# untitled.net
KiCad netlist of a schematic drawn in EAGLE
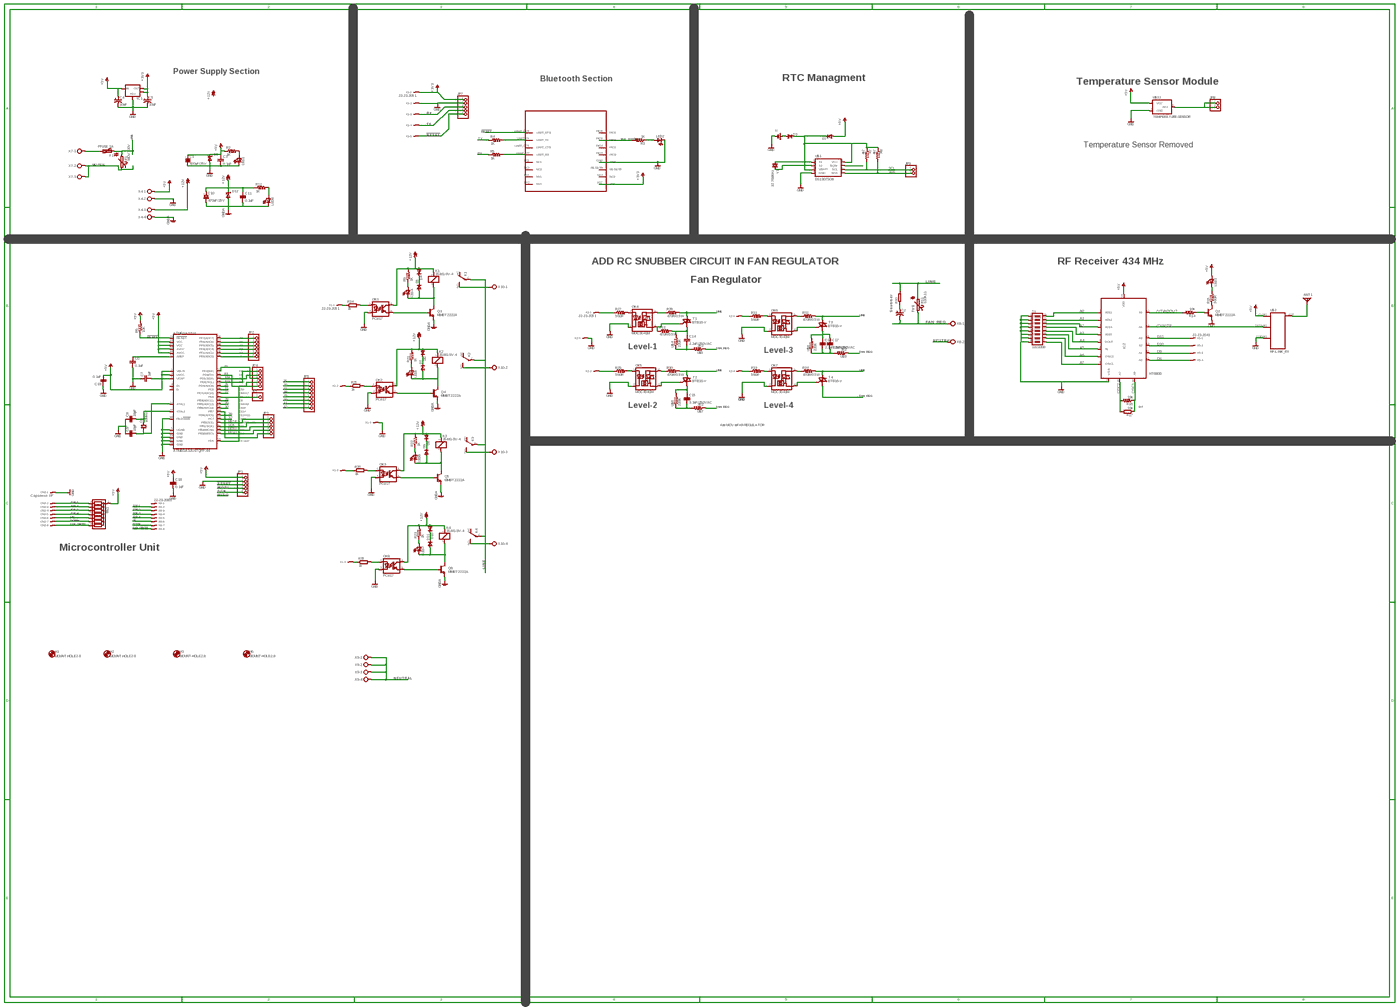
[diagram p0: schematic, sheet 1, overview]
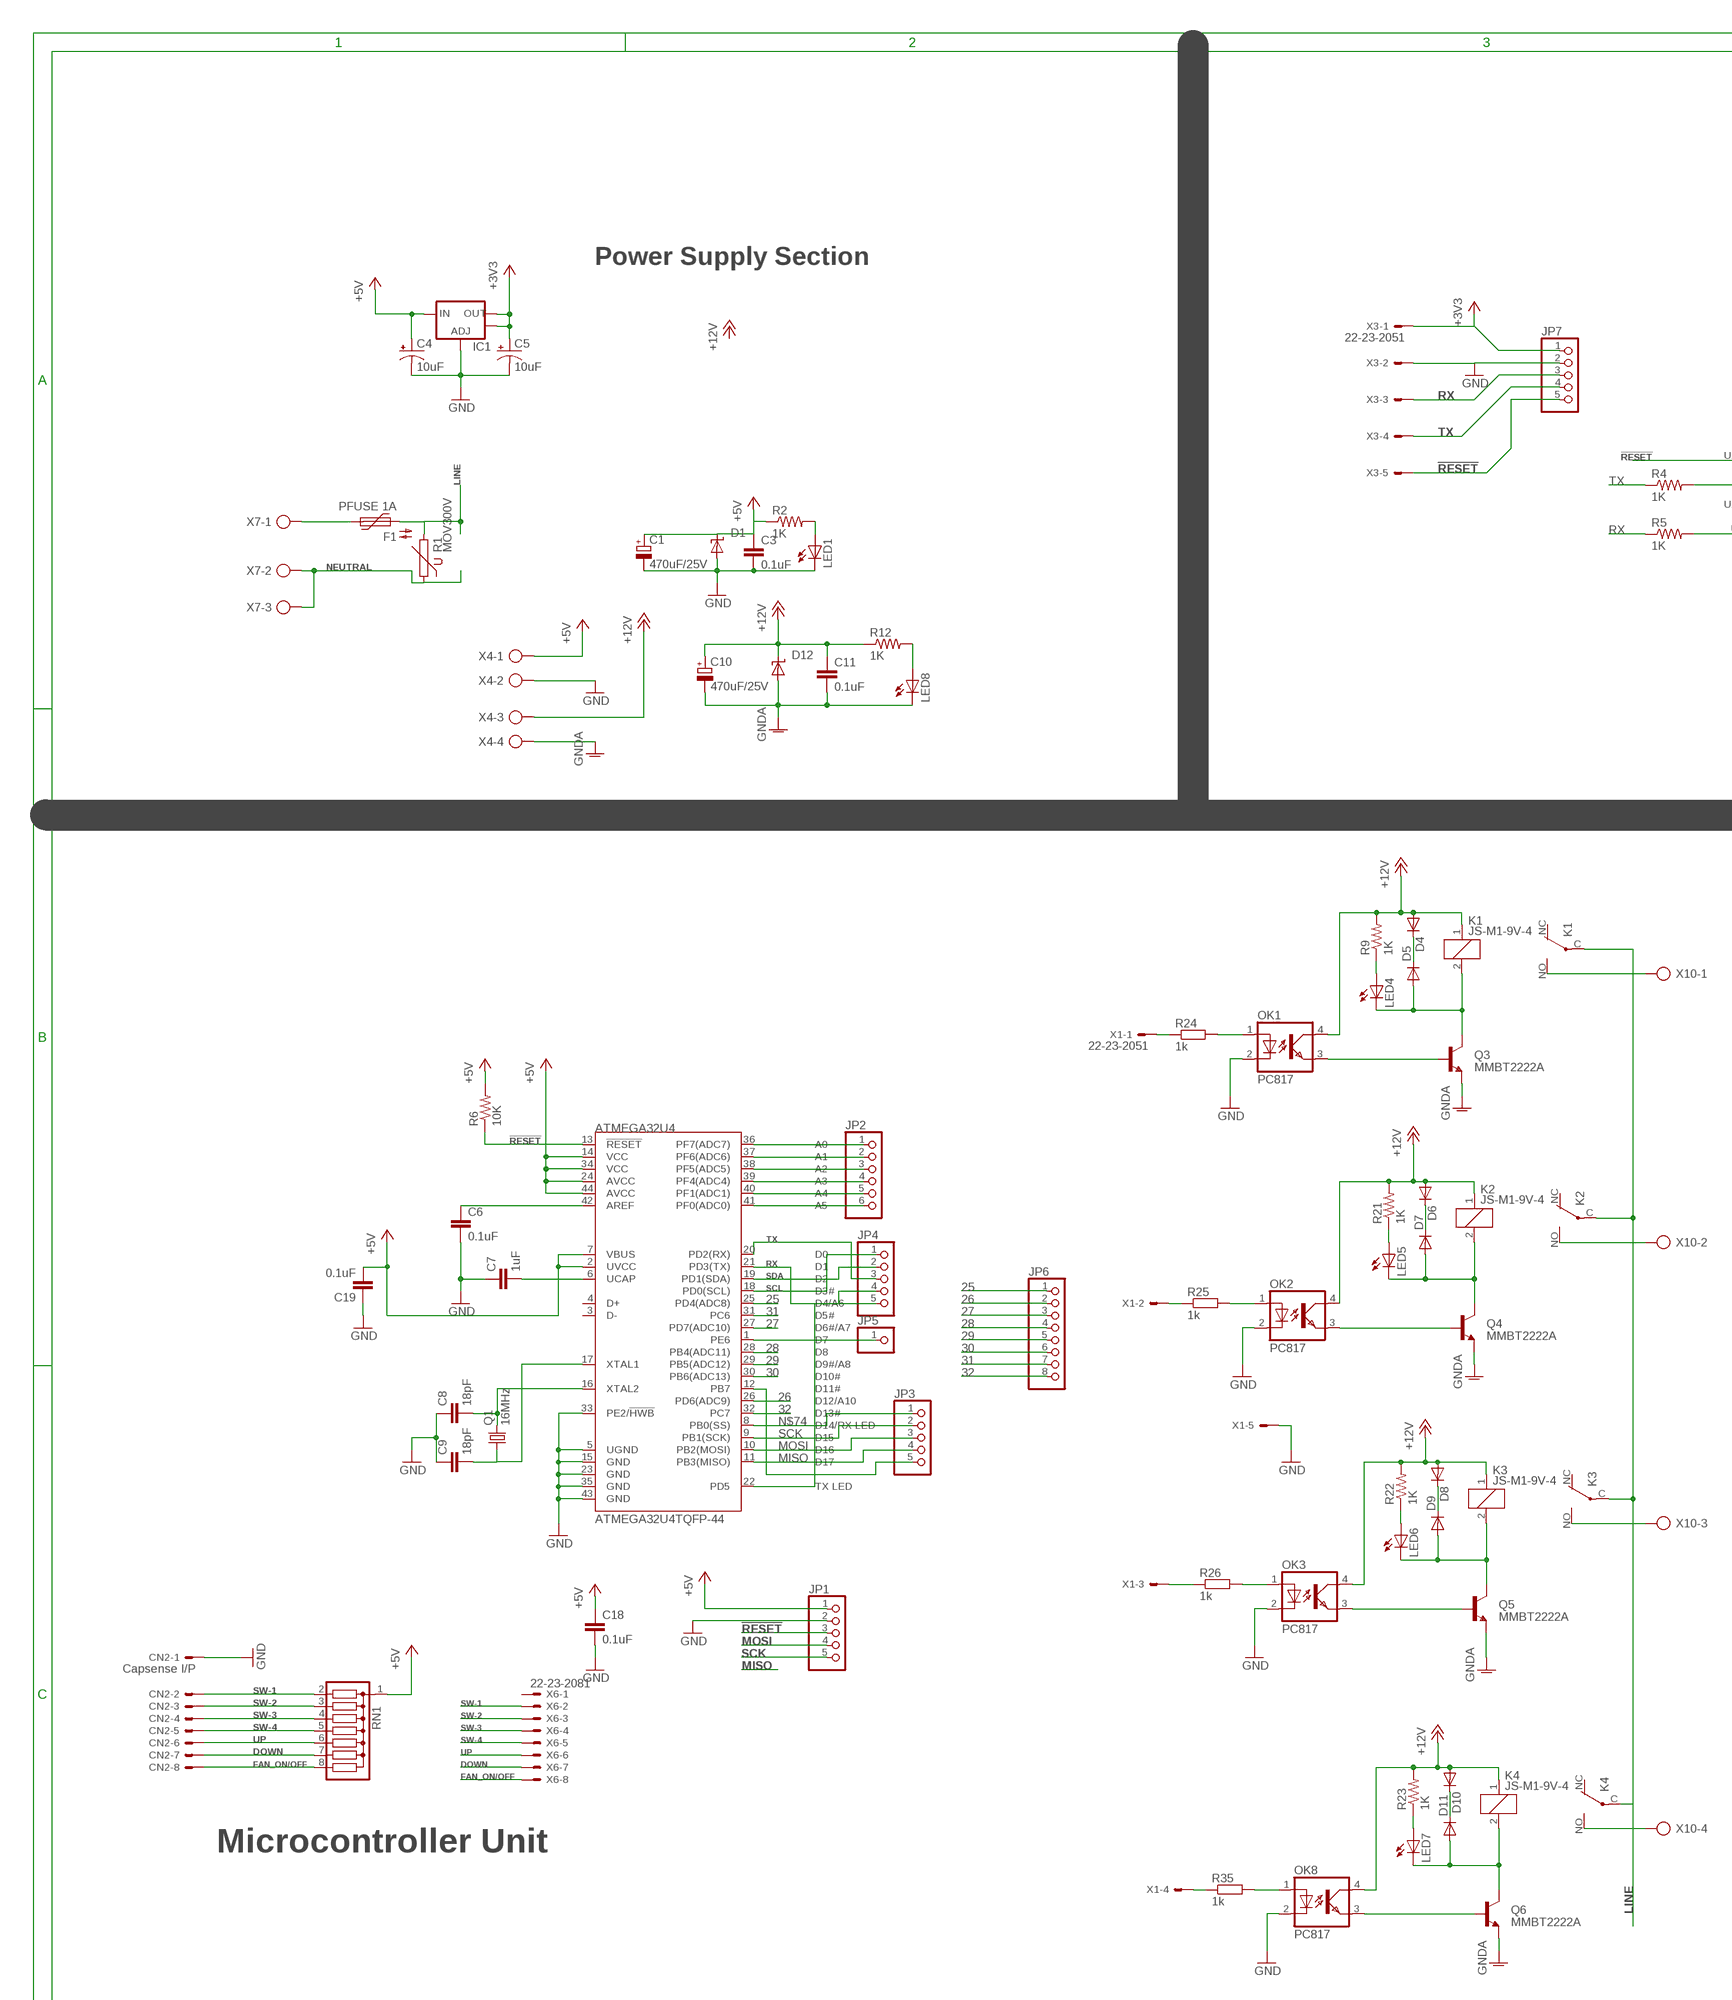
[diagram p1: schematic, sheet 1, part 1 of 6]
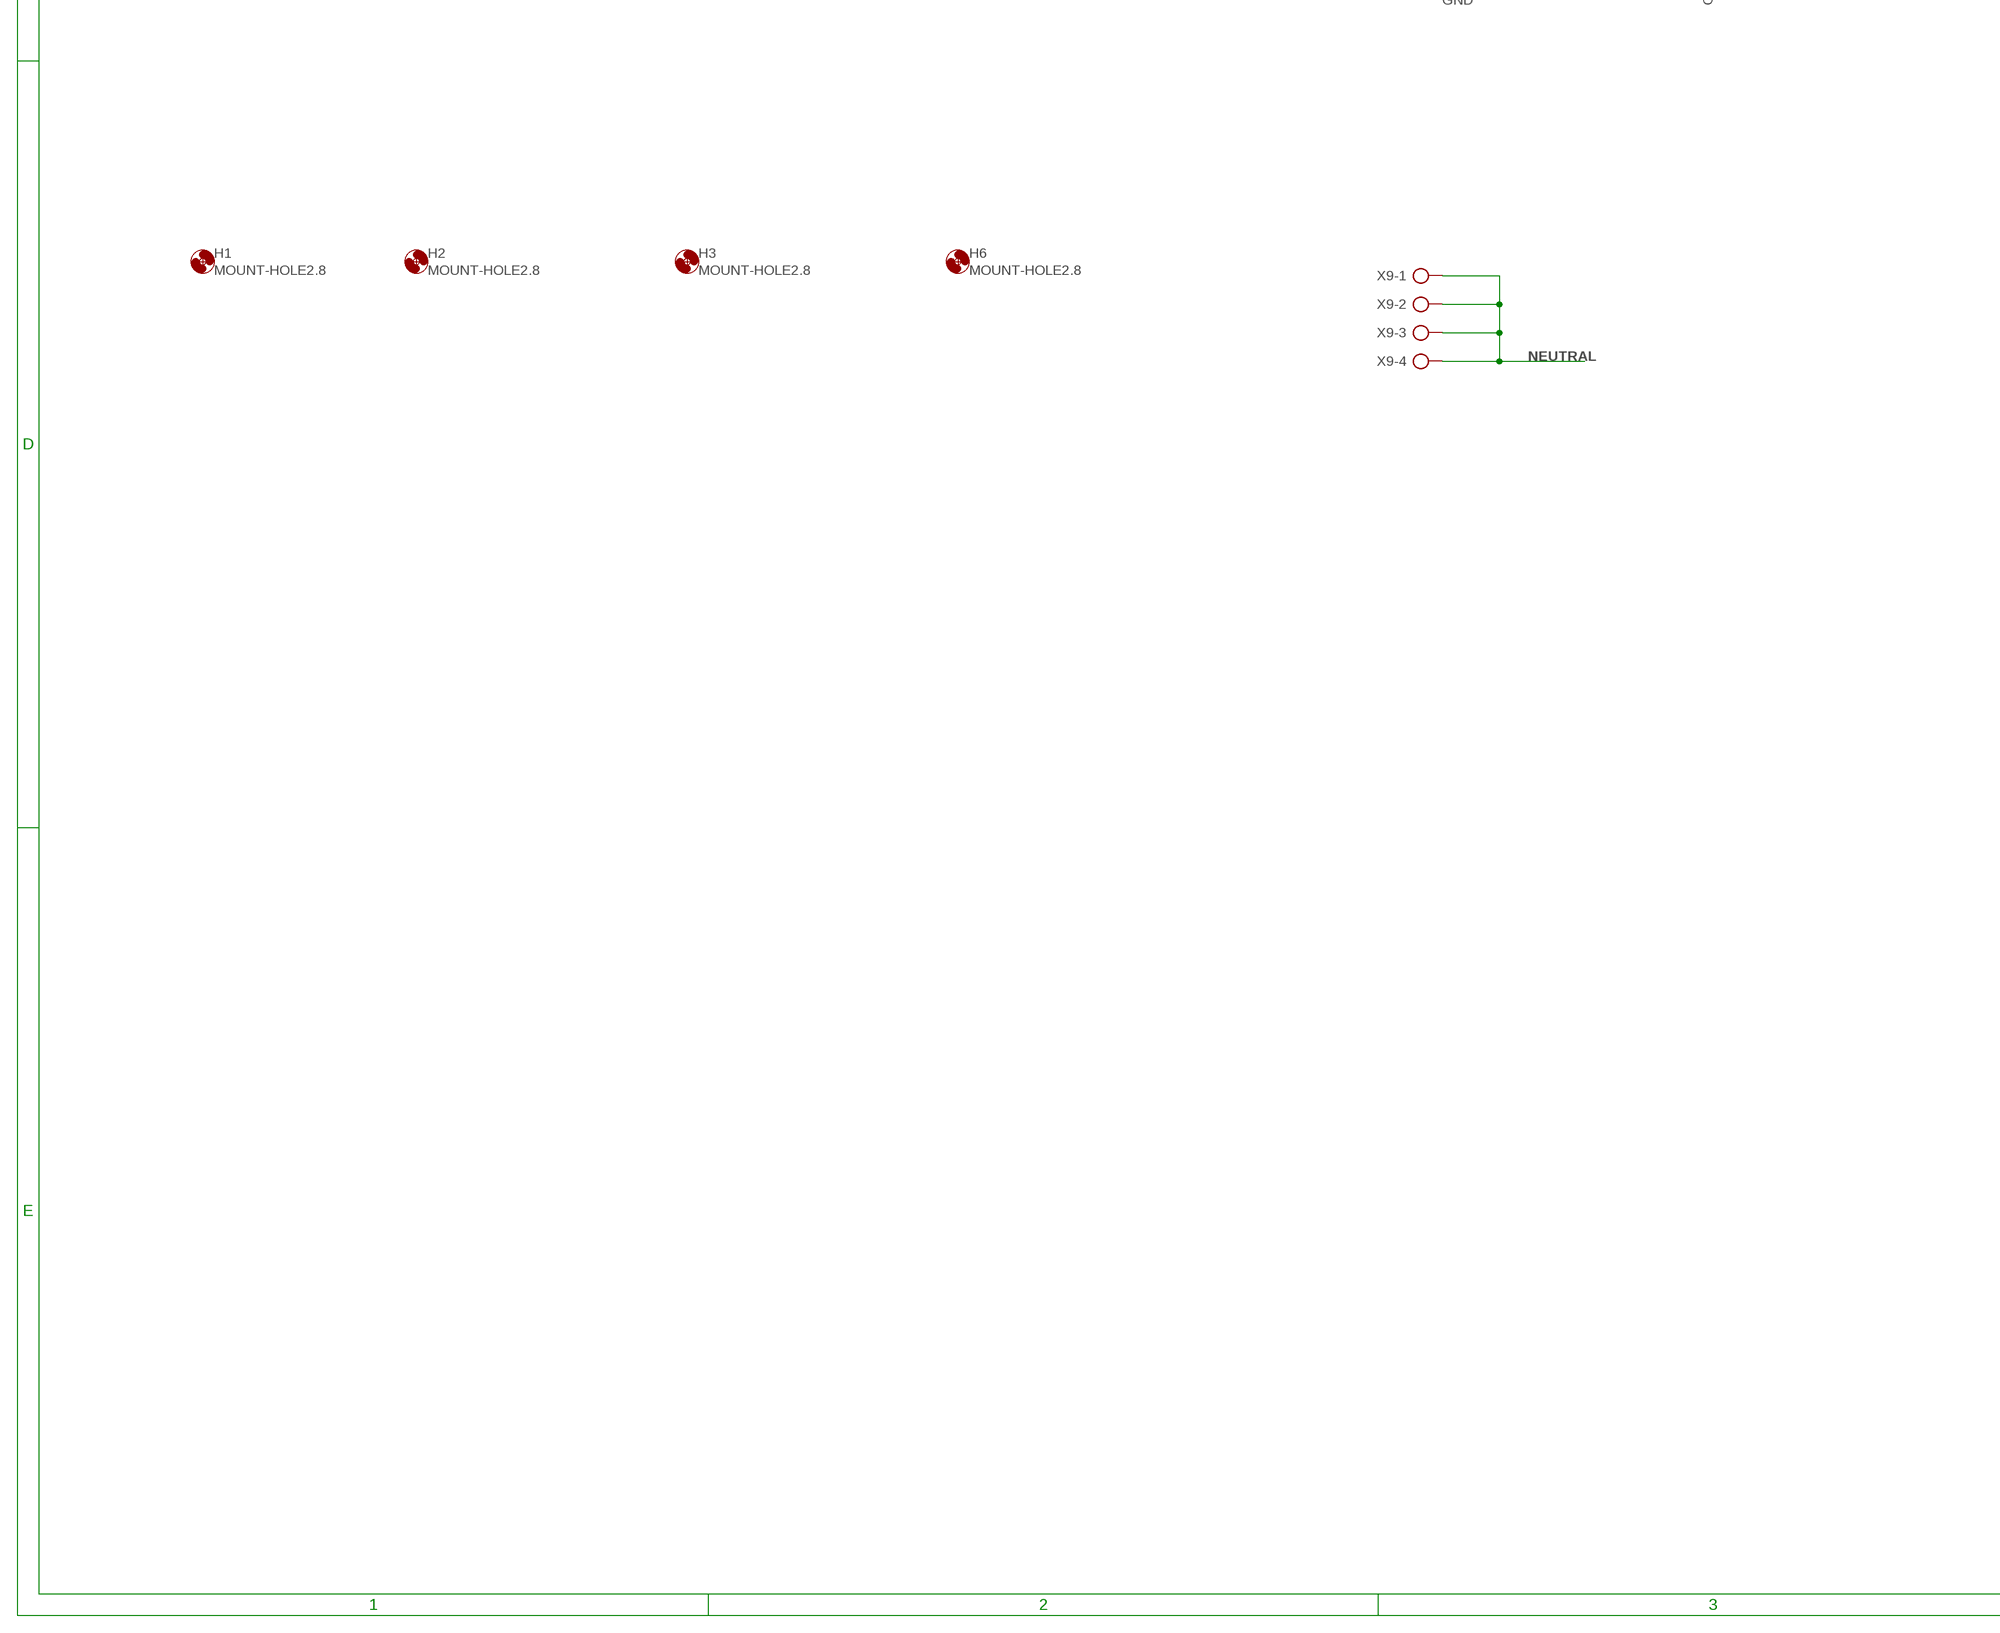
[diagram p2: schematic, sheet 1, part 2 of 6]
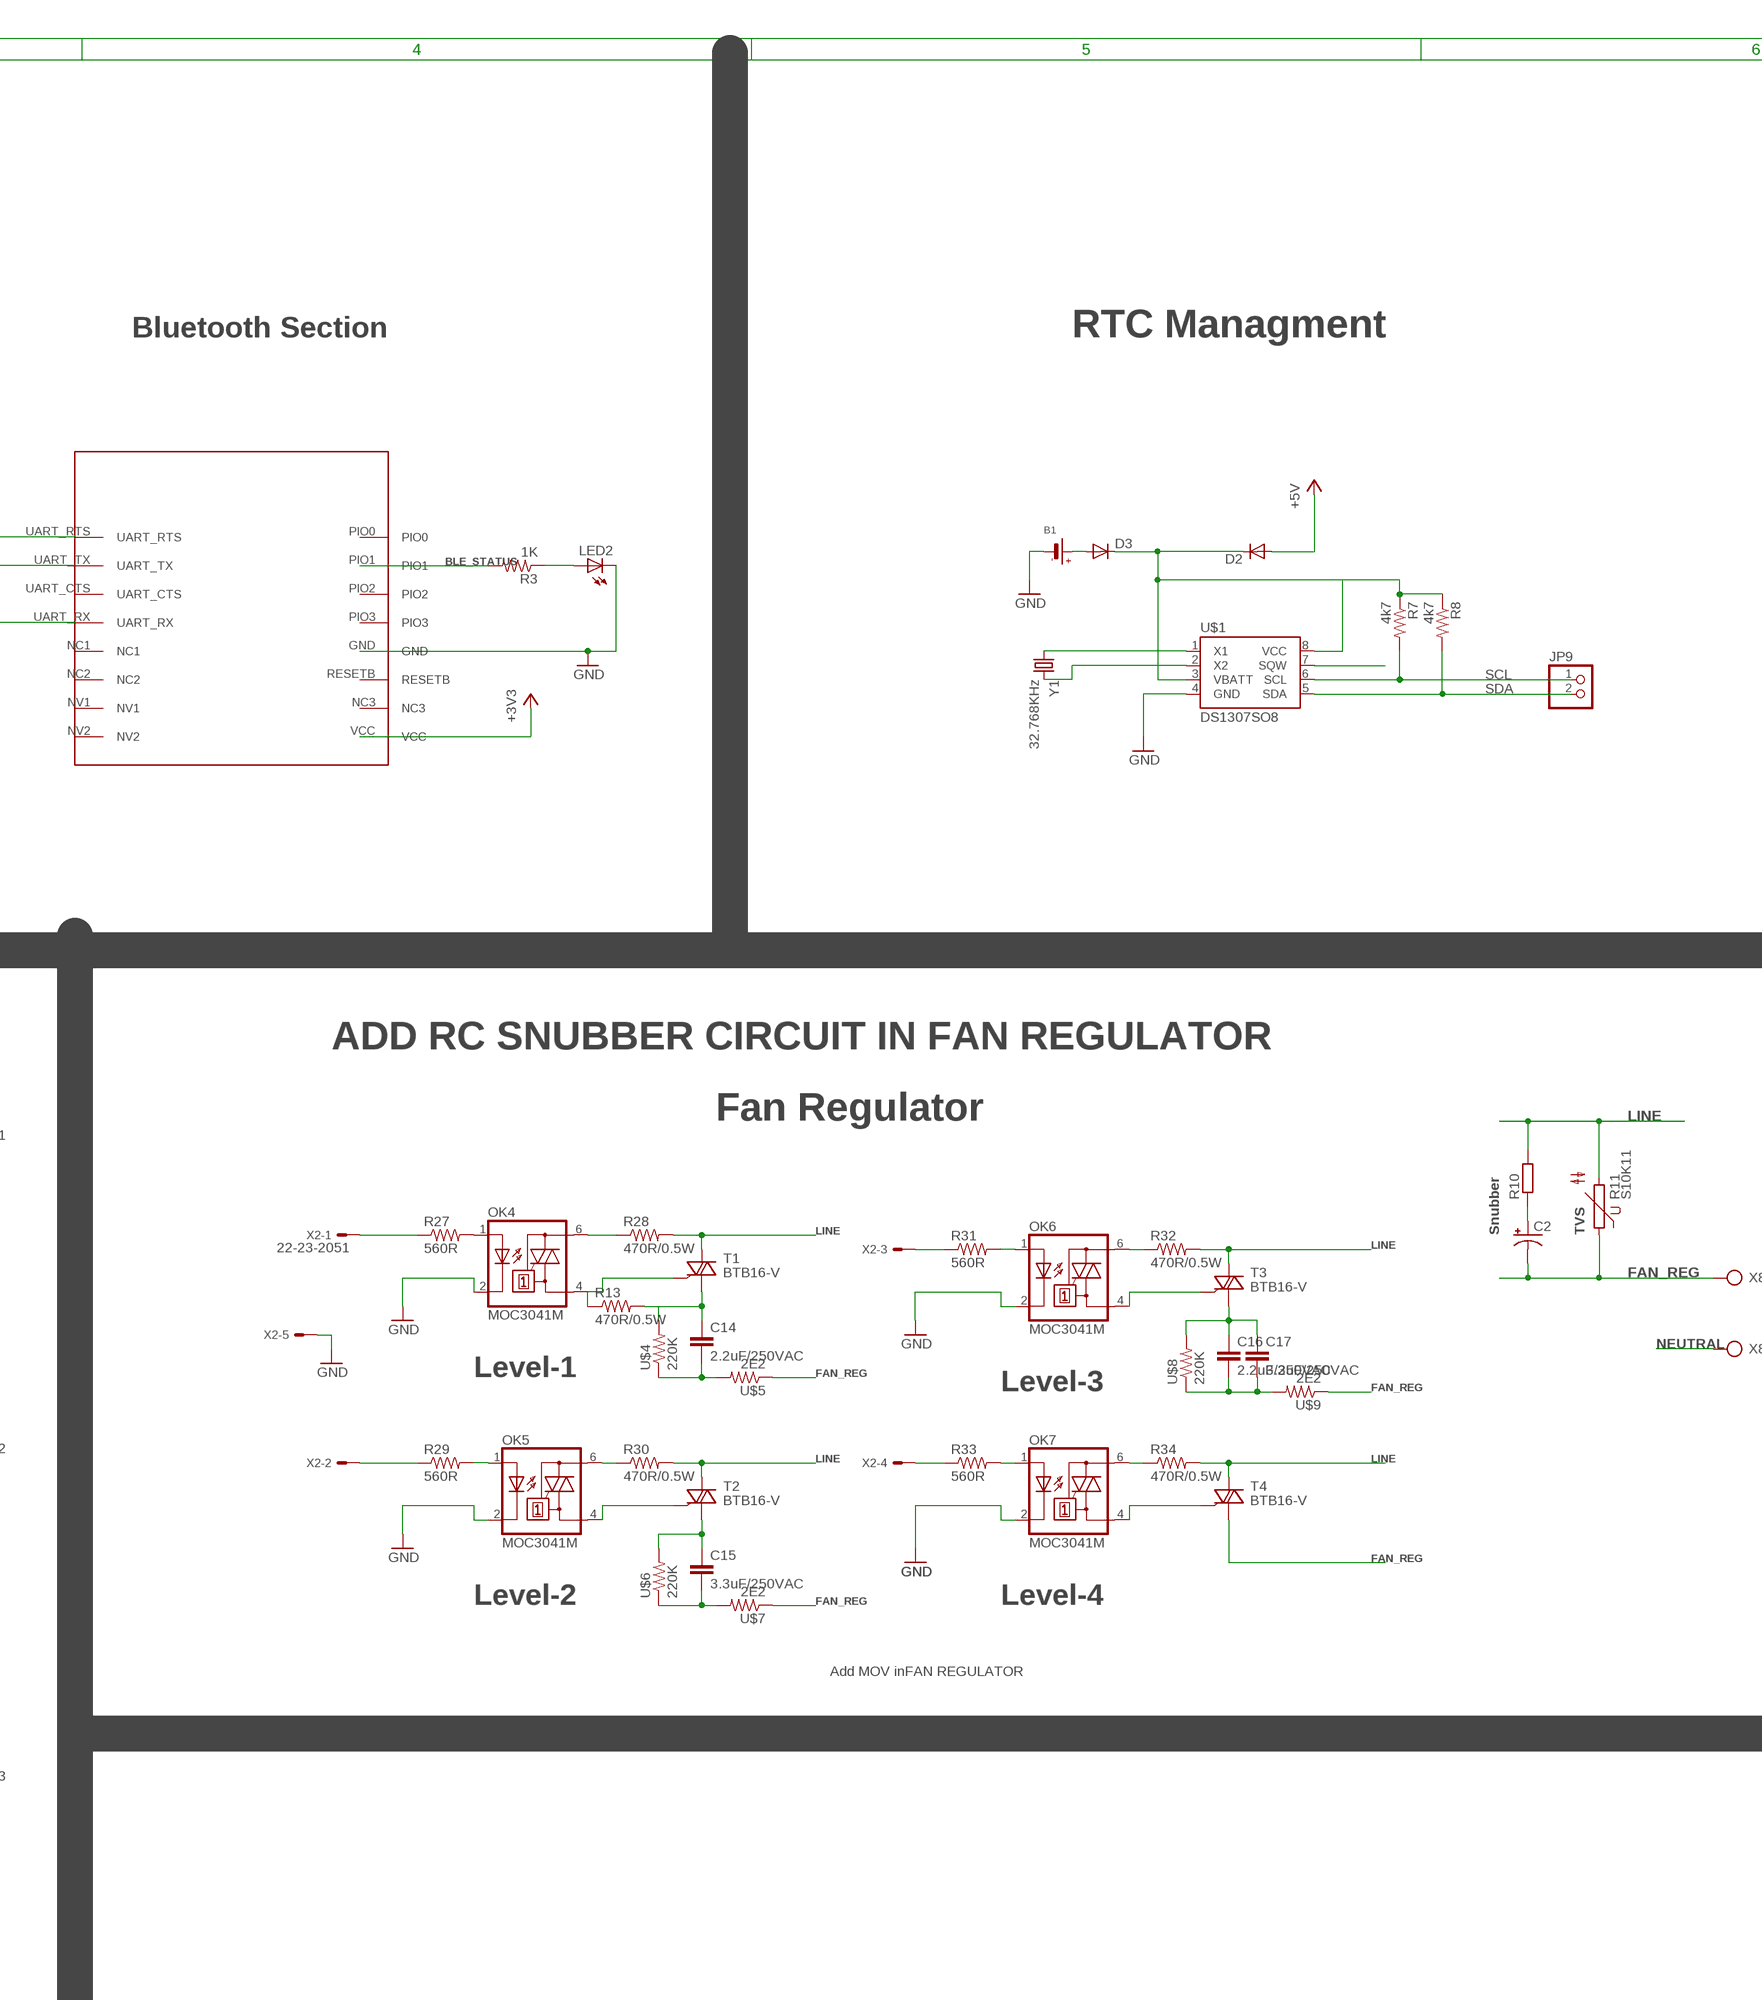
[diagram p3: schematic, sheet 1, part 3 of 6]
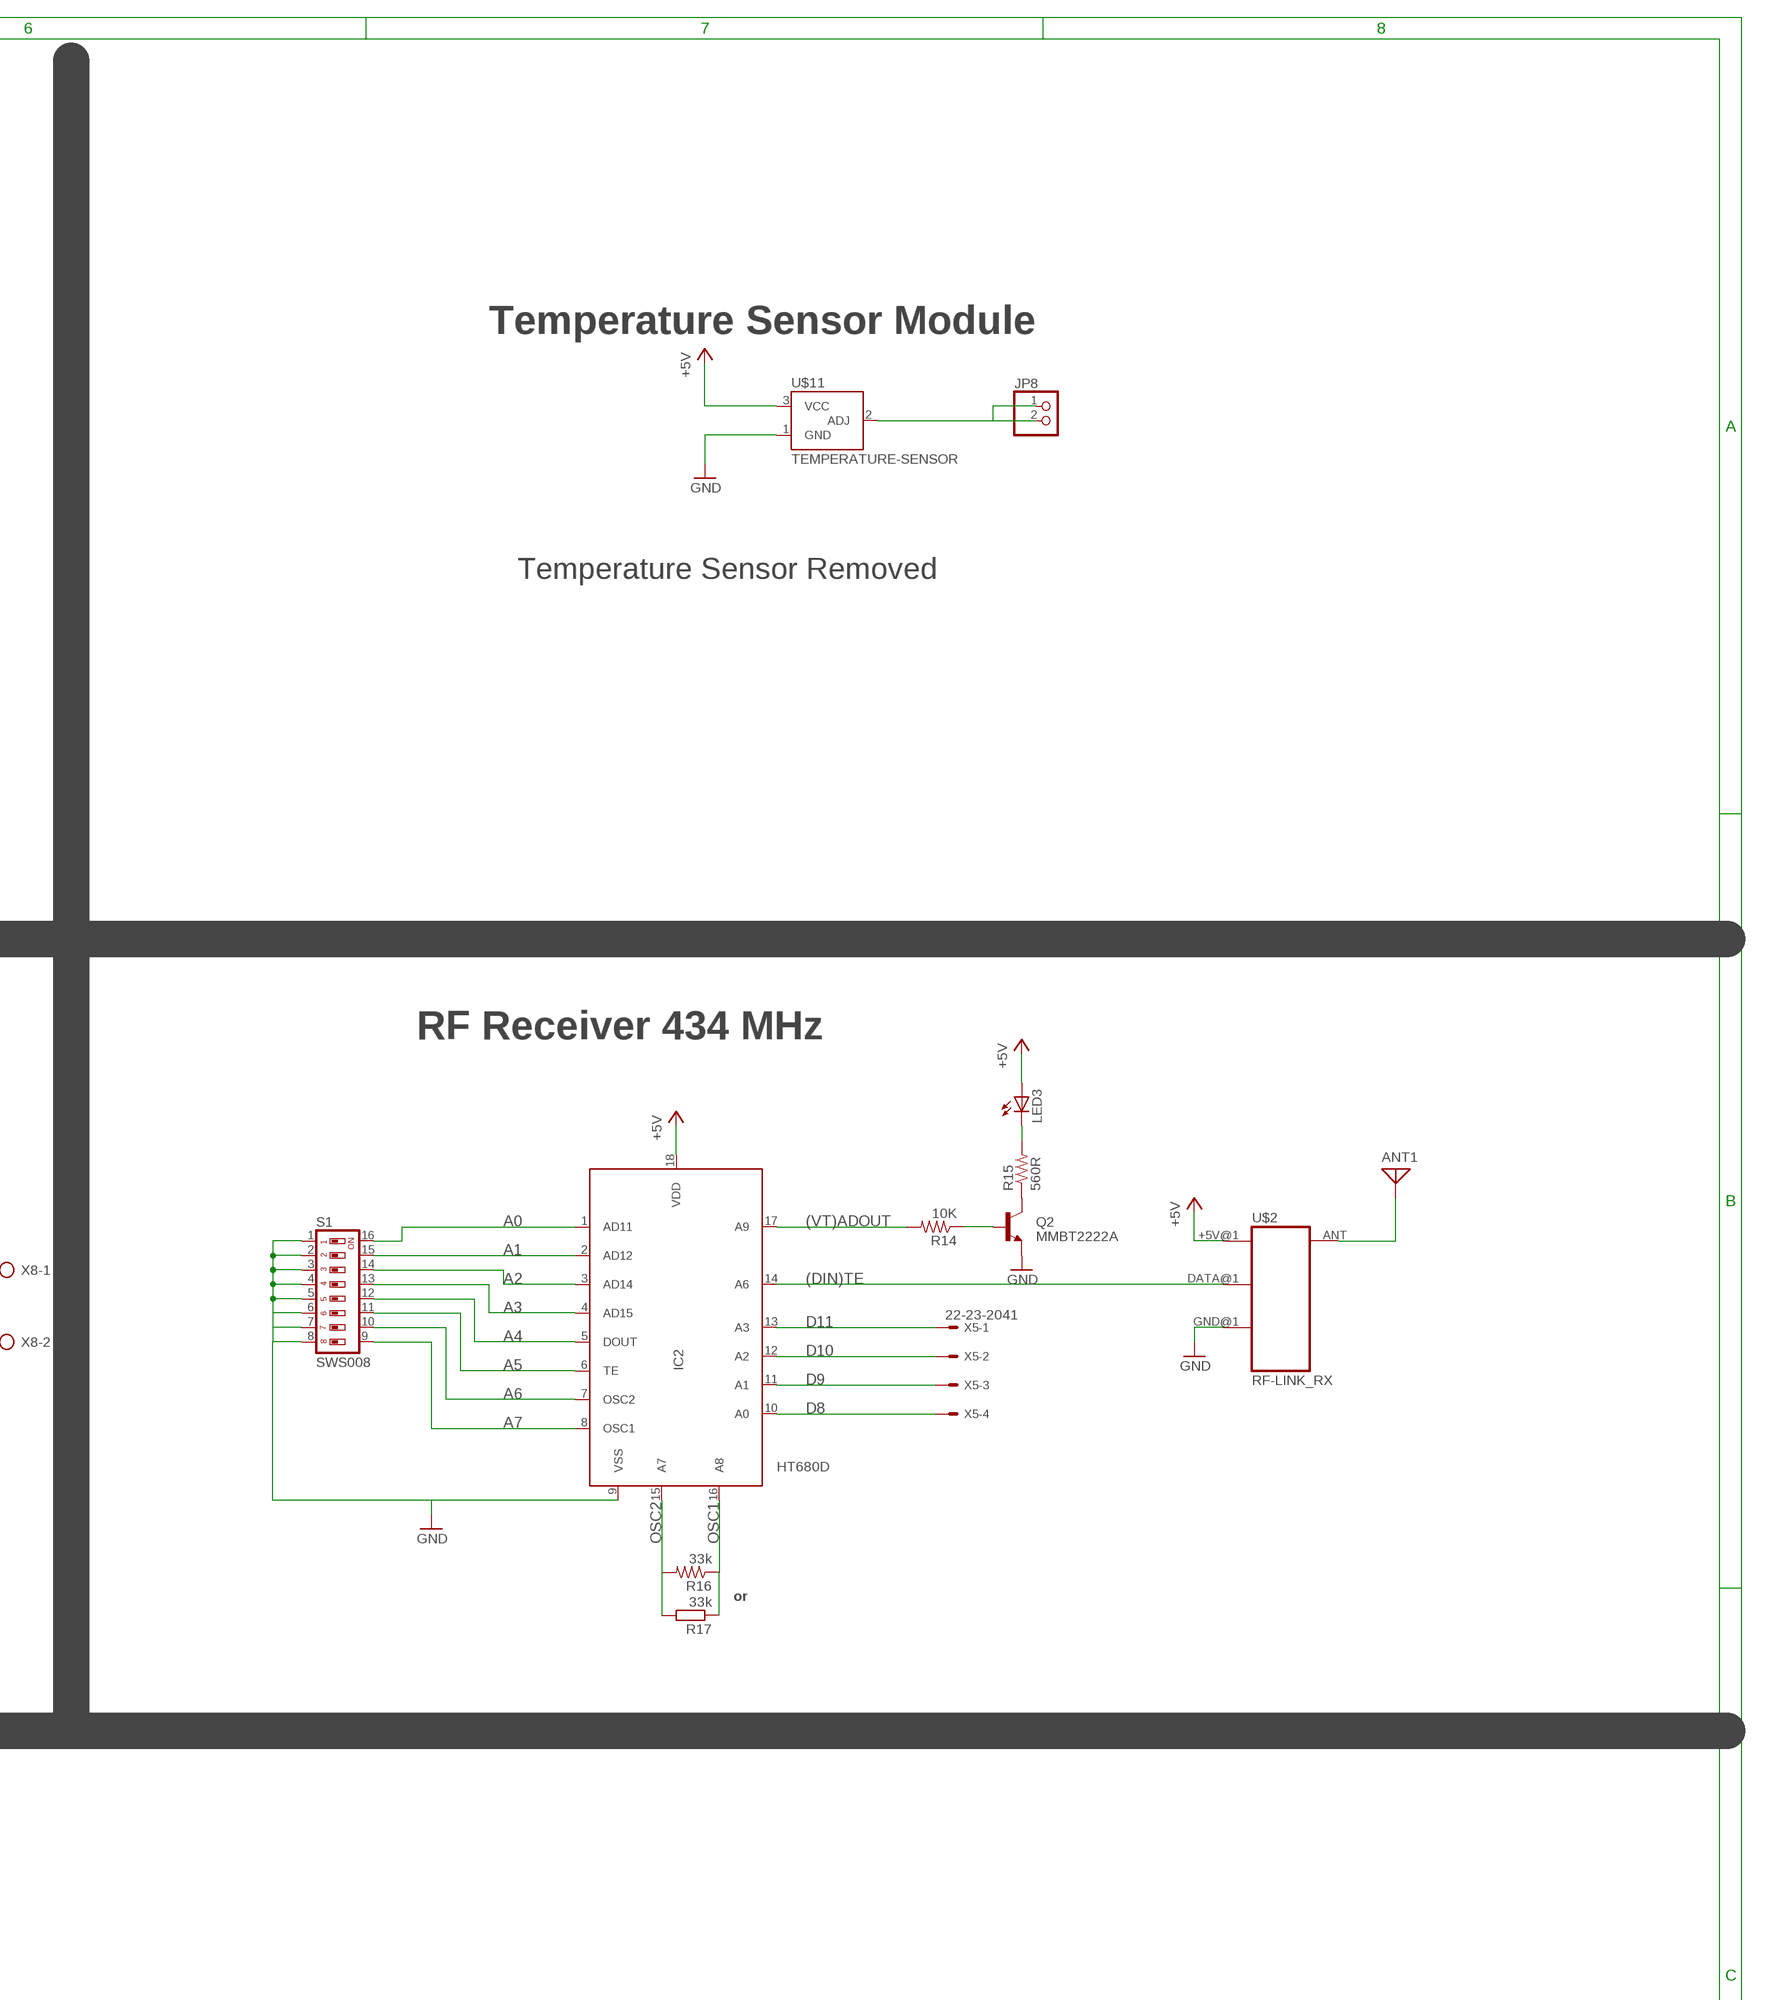
[diagram p4: schematic, sheet 1, part 4 of 6]
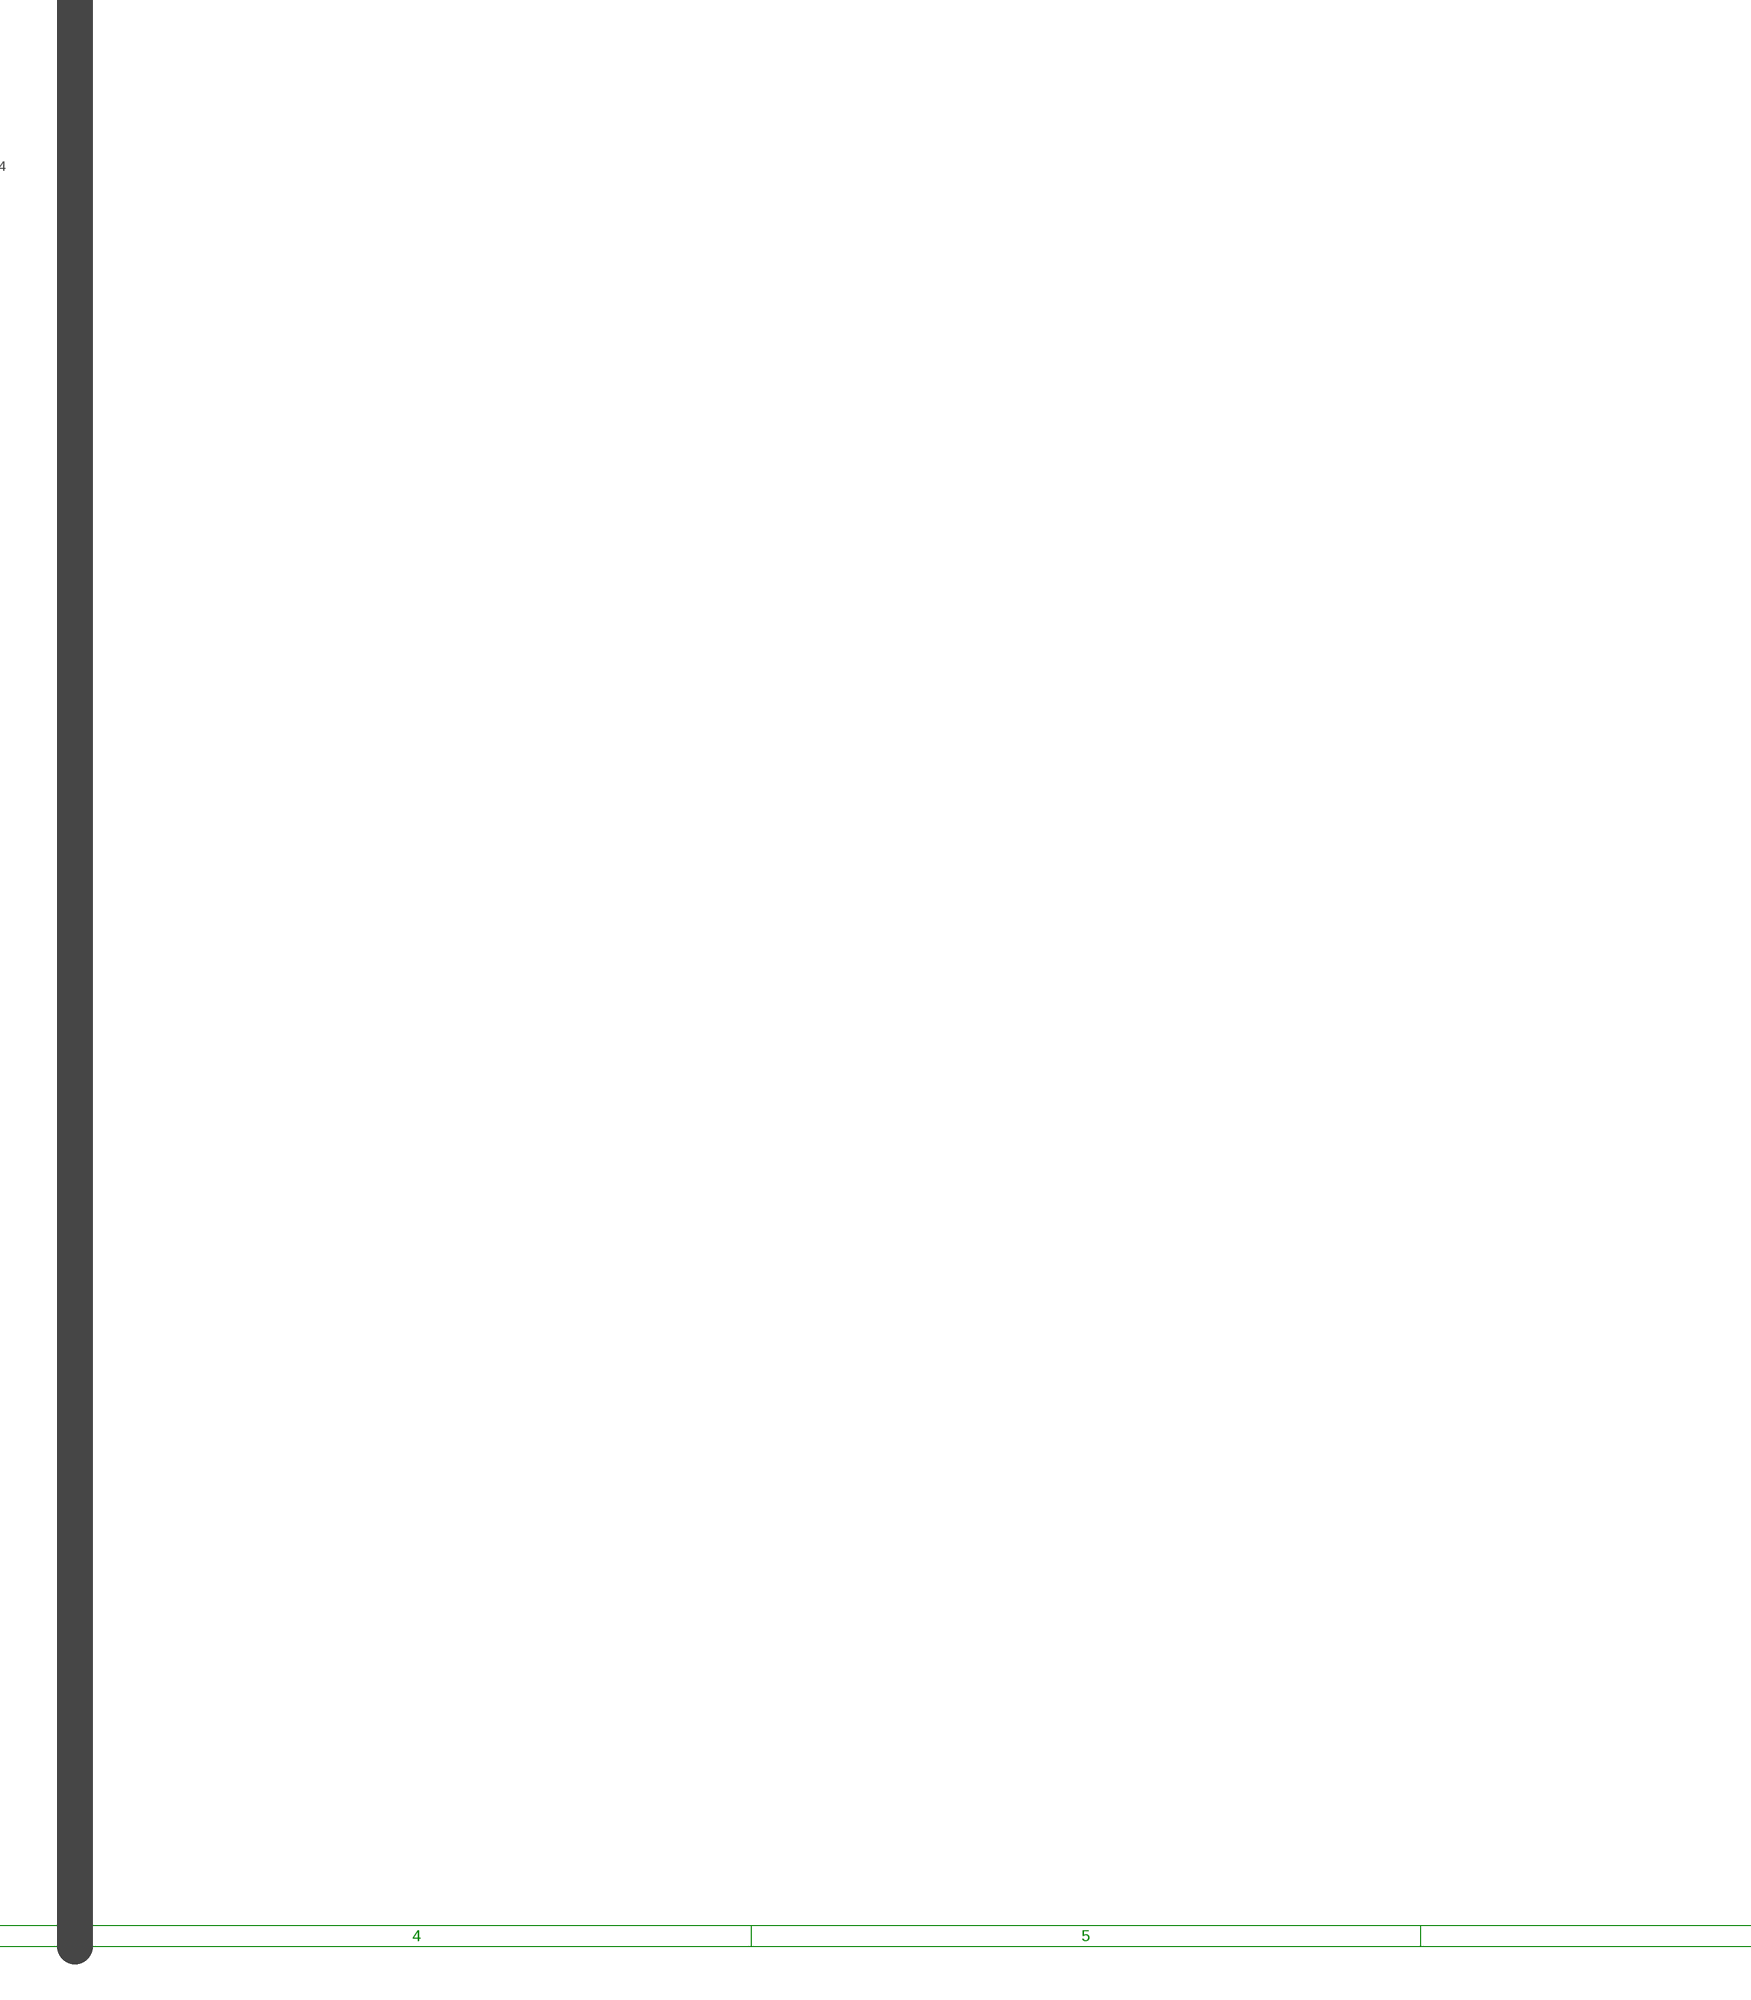
[diagram p5: schematic, sheet 1, part 5 of 6]
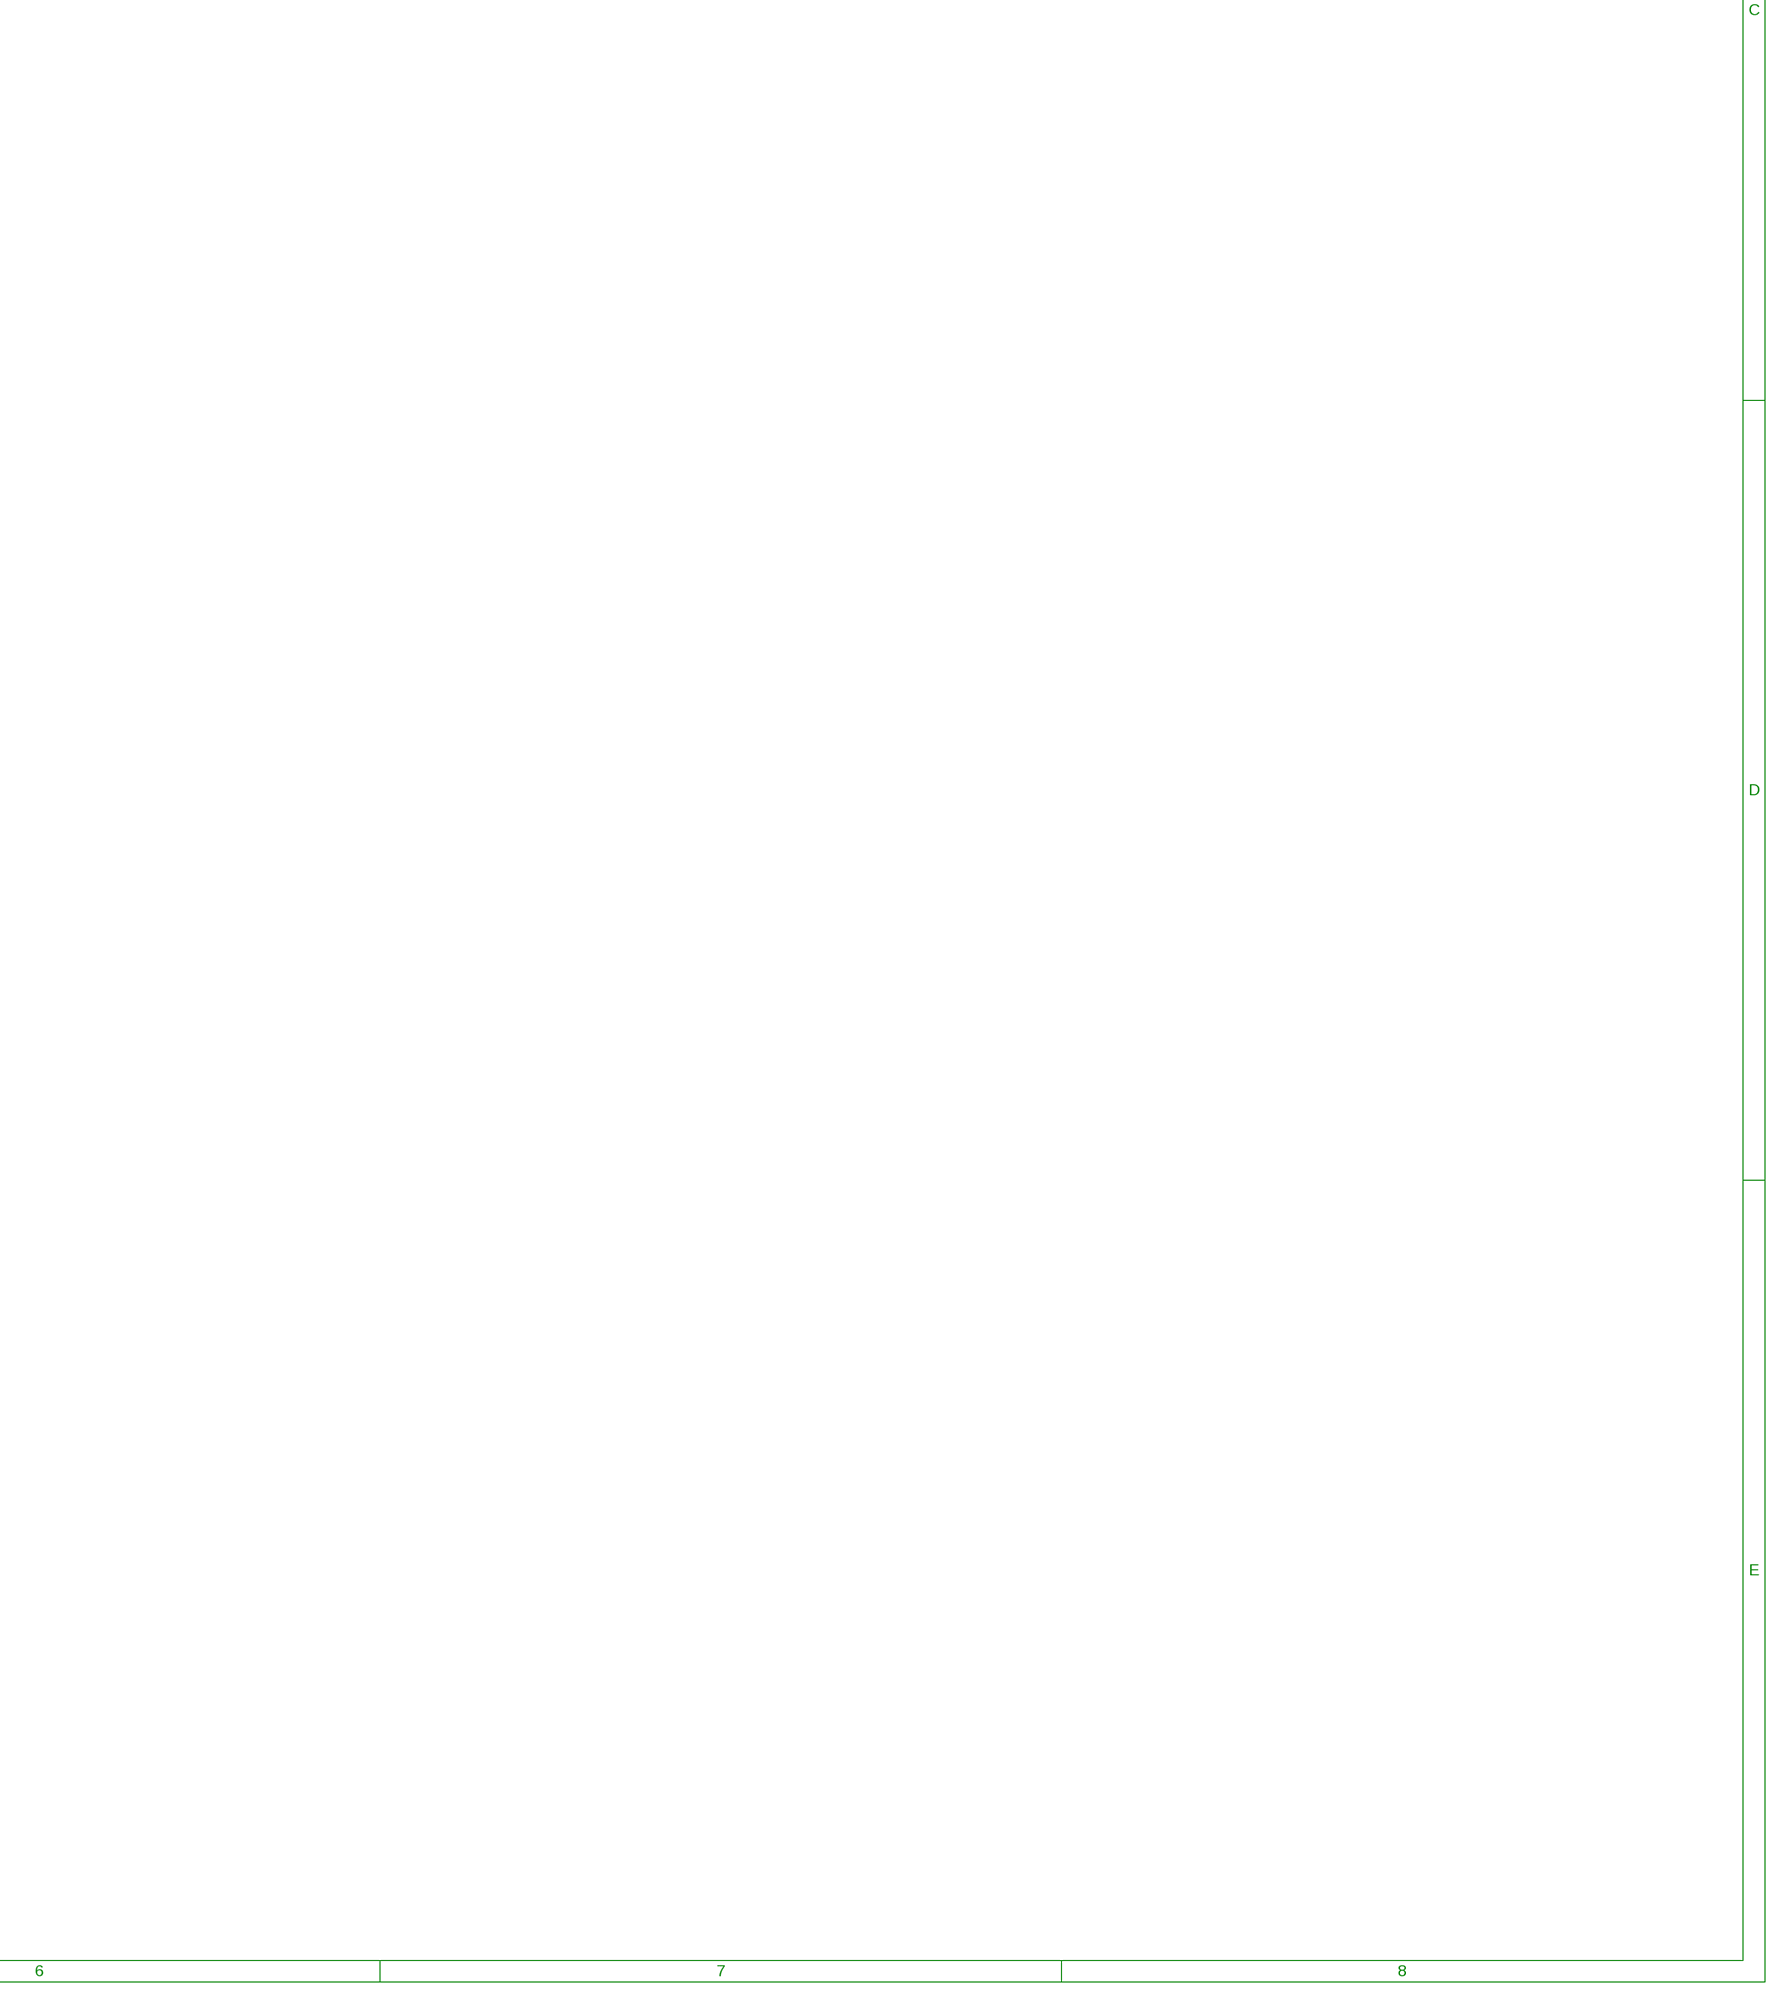
[diagram p6: schematic, sheet 1, part 6 of 6]

(export (version "E")
  (design (tool "Eeschema 10.0.6"))
  (components
    (comp (ref "ANT1")
      (value "ANTENNA")
      (footprint "eagle-import:PAD-01")
      (libsource (lib "eagle-import") (part "ANTENNA"))
    )
    (comp (ref "ATMEGA32U4")
      (value "ATMEGA32U4TQFP-44")
      (footprint "eagle-import:TQFP44")
      (libsource (lib "eagle-import") (part "ATMEGA32U4TQFP-44"))
    )
    (comp (ref "B1")
      (value "BATTERYCR2032")
      (footprint "eagle-import:CR2032")
      (libsource (lib "eagle-import") (part "BATTERYCR2032"))
    )
    (comp (ref "C1")
      (value "470uF/25V")
      (footprint "eagle-import:E5-8,5")
      (libsource (lib "eagle-import") (part "CPOL-EUE5-8.5"))
    )
    (comp (ref "C2")
      (value "CPOL-USE5-9VAXIAL")
      (footprint "eagle-import:E5R")
      (libsource (lib "eagle-import") (part "CPOL-USE5-9VAXIAL"))
    )
    (comp (ref "C3")
      (value "0.1uF")
      (footprint "eagle-import:1206")
      (libsource (lib "eagle-import") (part "1.0UF50V10%(1206)"))
    )
    (comp (ref "C4")
      (value "10uF")
      (footprint "eagle-import:EIA3216")
      (libsource (lib "eagle-import") (part "10UF-16V-10%(TANT)"))
    )
    (comp (ref "C5")
      (value "10uF")
      (footprint "eagle-import:EIA3216")
      (libsource (lib "eagle-import") (part "10UF-16V-10%(TANT)"))
    )
    (comp (ref "C6")
      (value "0.1uF")
      (footprint "eagle-import:1206")
      (libsource (lib "eagle-import") (part "CAP1206"))
    )
    (comp (ref "C7")
      (value "1uF")
      (footprint "eagle-import:1206")
      (libsource (lib "eagle-import") (part "CAP1206"))
    )
    (comp (ref "C8")
      (value "18pF")
      (footprint "eagle-import:1206")
      (libsource (lib "eagle-import") (part "CAP1206"))
    )
    (comp (ref "C9")
      (value "18pF")
      (footprint "eagle-import:1206")
      (libsource (lib "eagle-import") (part "CAP1206"))
    )
    (comp (ref "C10")
      (value "470uF/25V")
      (footprint "eagle-import:E5-8,5")
      (libsource (lib "eagle-import") (part "CPOL-EUE5-8.5"))
    )
    (comp (ref "C11")
      (value "0.1uF")
      (footprint "eagle-import:1206")
      (fields (field (name "PROD_ID") "CAP-09822"))
      (libsource (lib "eagle-import") (part "1.0UF50V10%(1206)"))
    )
    (comp (ref "C14")
      (value "2.2uF/250VAC")
      (footprint "eagle-import:C27.5B9")
      (libsource (lib "eagle-import") (part "C27/9"))
    )
    (comp (ref "C15")
      (value "3.3uF/250VAC")
      (footprint "eagle-import:C27.5B9")
      (libsource (lib "eagle-import") (part "C27/9"))
    )
    (comp (ref "C16")
      (value "2.2uF/250VAC")
      (footprint "eagle-import:C27.5B9")
      (libsource (lib "eagle-import") (part "C27/9"))
    )
    (comp (ref "C17")
      (value "3.3uF/250VAC")
      (footprint "eagle-import:C27.5B9")
      (libsource (lib "eagle-import") (part "C27/9"))
    )
    (comp (ref "C18")
      (value "0.1uF")
      (footprint "eagle-import:1206")
      (libsource (lib "eagle-import") (part "CAP1206"))
    )
    (comp (ref "C19")
      (value "0.1uF")
      (footprint "eagle-import:1206")
      (libsource (lib "eagle-import") (part "CAP1206"))
    )
    (comp (ref "CN2")
      (value "Capsense I/P")
      (footprint "eagle-import:22-23-2081")
      (fields (field (name "MF") "MOLEX") (field (name "MPN") "22-23-2081"))
      (libsource (lib "eagle-import") (part "22-23-2081"))
    )
    (comp (ref "D1")
      (value "SUPPRESSOR-SMBJ")
      (footprint "eagle-import:SMBJ")
      (libsource (lib "eagle-import") (part "SUPPRESSOR-SMBJ"))
    )
    (comp (ref "D2")
      (value "DIODE-D-5")
      (footprint "eagle-import:D-5")
      (libsource (lib "eagle-import") (part "DIODE-D-5"))
    )
    (comp (ref "D3")
      (value "DIODE-D-5")
      (footprint "eagle-import:D-5")
      (libsource (lib "eagle-import") (part "DIODE-D-5"))
    )
    (comp (ref "D4")
      (value "DIODE-D-2.5")
      (footprint "eagle-import:D-2.5")
      (libsource (lib "eagle-import") (part "DIODE-D-2.5"))
    )
    (comp (ref "D5")
      (value "DIODE-D-2.5")
      (footprint "eagle-import:D-2.5")
      (libsource (lib "eagle-import") (part "DIODE-D-2.5"))
    )
    (comp (ref "D6")
      (value "DIODE-D-2.5")
      (footprint "eagle-import:D-2.5")
      (libsource (lib "eagle-import") (part "DIODE-D-2.5"))
    )
    (comp (ref "D7")
      (value "DIODE-D-2.5")
      (footprint "eagle-import:D-2.5")
      (libsource (lib "eagle-import") (part "DIODE-D-2.5"))
    )
    (comp (ref "D8")
      (value "DIODE-D-2.5")
      (footprint "eagle-import:D-2.5")
      (libsource (lib "eagle-import") (part "DIODE-D-2.5"))
    )
    (comp (ref "D9")
      (value "DIODE-D-2.5")
      (footprint "eagle-import:D-2.5")
      (libsource (lib "eagle-import") (part "DIODE-D-2.5"))
    )
    (comp (ref "D10")
      (value "DIODE-D-2.5")
      (footprint "eagle-import:D-2.5")
      (libsource (lib "eagle-import") (part "DIODE-D-2.5"))
    )
    (comp (ref "D11")
      (value "DIODE-D-2.5")
      (footprint "eagle-import:D-2.5")
      (libsource (lib "eagle-import") (part "DIODE-D-2.5"))
    )
    (comp (ref "D12")
      (value "SUPPRESSOR-SMBJ")
      (footprint "eagle-import:SMBJ")
      (libsource (lib "eagle-import") (part "SUPPRESSOR-SMBJ"))
    )
    (comp (ref "F1")
      (value "PFUSE 1A")
      (footprint "eagle-import:MF-5,1B")
      (libsource (lib "eagle-import") (part "MF-R055-5,1B"))
    )
    (comp (ref "H1")
      (value "MOUNT-HOLE2.8")
      (footprint "eagle-import:2,8")
      (libsource (lib "eagle-import") (part "MOUNT-HOLE2.8"))
    )
    (comp (ref "H2")
      (value "MOUNT-HOLE2.8")
      (footprint "eagle-import:2,8")
      (libsource (lib "eagle-import") (part "MOUNT-HOLE2.8"))
    )
    (comp (ref "H3")
      (value "MOUNT-HOLE2.8")
      (footprint "eagle-import:2,8")
      (libsource (lib "eagle-import") (part "MOUNT-HOLE2.8"))
    )
    (comp (ref "H6")
      (value "MOUNT-HOLE2.8")
      (footprint "eagle-import:2,8")
      (libsource (lib "eagle-import") (part "MOUNT-HOLE2.8"))
    )
    (comp (ref "IC1")
      (value "V_REG_LM1117SOT223")
      (footprint "eagle-import:SOT223")
      (libsource (lib "eagle-import") (part "V_REG_LM1117SOT223"))
    )
    (comp (ref "IC2")
      (value "HT680D")
      (footprint "eagle-import:SOP18")
      (libsource (lib "eagle-import") (part "HT680D"))
    )
    (comp (ref "JP1")
      (value "PINHD-1X5")
      (footprint "eagle-import:1X05")
      (libsource (lib "eagle-import") (part "PINHD-1X5"))
    )
    (comp (ref "JP2")
      (value "PINHD-1X6")
      (footprint "eagle-import:1X06")
      (libsource (lib "eagle-import") (part "PINHD-1X6"))
    )
    (comp (ref "JP3")
      (value "PINHD-1X5")
      (footprint "eagle-import:1X05")
      (libsource (lib "eagle-import") (part "PINHD-1X5"))
    )
    (comp (ref "JP4")
      (value "PINHD-1X5")
      (footprint "eagle-import:1X05")
      (libsource (lib "eagle-import") (part "PINHD-1X5"))
    )
    (comp (ref "JP5")
      (value "PINHD-1X1")
      (footprint "eagle-import:1X01")
      (libsource (lib "eagle-import") (part "PINHD-1X1"))
    )
    (comp (ref "JP6")
      (value "PINHD-1X8")
      (footprint "eagle-import:1X08")
      (libsource (lib "eagle-import") (part "PINHD-1X8"))
    )
    (comp (ref "JP7")
      (value "PINHD-1X5")
      (footprint "eagle-import:1X05")
      (libsource (lib "eagle-import") (part "PINHD-1X5"))
    )
    (comp (ref "JP8")
      (value "PINHD-1X2")
      (footprint "eagle-import:1X02")
      (libsource (lib "eagle-import") (part "PINHD-1X2"))
    )
    (comp (ref "JP9")
      (value "PINHD-1X2")
      (footprint "eagle-import:1X02")
      (libsource (lib "eagle-import") (part "PINHD-1X2"))
    )
    (comp (ref "K1")
      (value "JS-M1-9V-4")
      (footprint "eagle-import:JS-M")
      (libsource (lib "eagle-import") (part "JS-M1-9V-4"))
    )
    (comp (ref "K2")
      (value "JS-M1-9V-4")
      (footprint "eagle-import:JS-M")
      (libsource (lib "eagle-import") (part "JS-M1-9V-4"))
    )
    (comp (ref "K3")
      (value "JS-M1-9V-4")
      (footprint "eagle-import:JS-M")
      (libsource (lib "eagle-import") (part "JS-M1-9V-4"))
    )
    (comp (ref "K4")
      (value "JS-M1-9V-4")
      (footprint "eagle-import:JS-M")
      (libsource (lib "eagle-import") (part "JS-M1-9V-4"))
    )
    (comp (ref "LED1")
      (value "LED3MM")
      (footprint "eagle-import:LED3MM")
      (libsource (lib "eagle-import") (part "LED3MM"))
    )
    (comp (ref "LED2")
      (value "LEDSML1206")
      (footprint "eagle-import:SML1206")
      (libsource (lib "eagle-import") (part "LEDSML1206"))
    )
    (comp (ref "LED3")
      (value "LED3MM")
      (footprint "eagle-import:LED3MM")
      (libsource (lib "eagle-import") (part "LED3MM"))
    )
    (comp (ref "LED4")
      (value "LED3MM")
      (footprint "eagle-import:LED3MM")
      (libsource (lib "eagle-import") (part "LED3MM"))
    )
    (comp (ref "LED5")
      (value "LED3MM")
      (footprint "eagle-import:LED3MM")
      (libsource (lib "eagle-import") (part "LED3MM"))
    )
    (comp (ref "LED6")
      (value "LED3MM")
      (footprint "eagle-import:LED3MM")
      (libsource (lib "eagle-import") (part "LED3MM"))
    )
    (comp (ref "LED7")
      (value "LED3MM")
      (footprint "eagle-import:LED3MM")
      (libsource (lib "eagle-import") (part "LED3MM"))
    )
    (comp (ref "LED8")
      (value "LED3MM")
      (footprint "eagle-import:LED3MM")
      (libsource (lib "eagle-import") (part "LED3MM"))
    )
    (comp (ref "OK1")
      (value "PC817")
      (footprint "eagle-import:DIL04")
      (fields (field (name "MPN") "PC817X4J000F"))
      (libsource (lib "eagle-import") (part "PC817"))
    )
    (comp (ref "OK2")
      (value "PC817")
      (footprint "eagle-import:DIL04")
      (fields (field (name "MPN") "PC817X4J000F"))
      (libsource (lib "eagle-import") (part "PC817"))
    )
    (comp (ref "OK3")
      (value "PC817")
      (footprint "eagle-import:DIL04")
      (fields (field (name "MPN") "PC817X4J000F"))
      (libsource (lib "eagle-import") (part "PC817"))
    )
    (comp (ref "OK4")
      (value "MOC3041M")
      (footprint "eagle-import:DIL06")
      (fields
        (field (name "MF") "FAIRCHILD SEMICONDUCTOR")
        (field (name "MPN") "MOC3041M")
        (field (name "OC_FARNELL") "1086677")
        (field (name "OC_NEWARK") "78K6090")
      )
      (libsource (lib "eagle-import") (part "MOC3041M"))
    )
    (comp (ref "OK5")
      (value "MOC3041M")
      (footprint "eagle-import:DIL06")
      (fields
        (field (name "MF") "FAIRCHILD SEMICONDUCTOR")
        (field (name "MF_1") "FAIRCHILD SEMICONDUCTOR")
        (field (name "MPN") "MOC3031SM")
        (field (name "OC_FARNELL") "unknown")
        (field (name "OC_NEWARK") "34C1335")
      )
      (libsource (lib "eagle-import") (part "MOC3041M"))
    )
    (comp (ref "OK6")
      (value "MOC3041M")
      (footprint "eagle-import:DIL06")
      (fields
        (field (name "MF") "FAIRCHILD SEMICONDUCTOR")
        (field (name "MF_1") "FAIRCHILD SEMICONDUCTOR")
        (field (name "MPN") "MOC3031SM")
        (field (name "OC_FARNELL") "unknown")
        (field (name "OC_NEWARK") "34C1335")
      )
      (libsource (lib "eagle-import") (part "MOC3041M"))
    )
    (comp (ref "OK7")
      (value "MOC3041M")
      (footprint "eagle-import:DIL06")
      (fields
        (field (name "MF") "FAIRCHILD SEMICONDUCTOR")
        (field (name "MF_1") "FAIRCHILD SEMICONDUCTOR")
        (field (name "MPN") "MOC3031SM")
        (field (name "OC_FARNELL") "unknown")
        (field (name "OC_NEWARK") "34C1335")
      )
      (libsource (lib "eagle-import") (part "MOC3041M"))
    )
    (comp (ref "OK8")
      (value "PC817")
      (footprint "eagle-import:DIL04")
      (fields (field (name "MPN") "PC817X4J000F"))
      (libsource (lib "eagle-import") (part "PC817"))
    )
    (comp (ref "Q1")
      (value "16MHz")
      (footprint "eagle-import:HC49UP")
      (libsource (lib "eagle-import") (part "CRYSTALHC49UP"))
    )
    (comp (ref "Q2")
      (value "MMBT2222A")
      (footprint "eagle-import:SOT23-3")
      (libsource (lib "eagle-import") (part "TRANSISTOR_NPNMMBT2222A"))
    )
    (comp (ref "Q3")
      (value "MMBT2222A")
      (footprint "eagle-import:TO-92-AMMO")
      (libsource (lib "eagle-import") (part "TRANSISTOR_NPNBC547"))
    )
    (comp (ref "Q4")
      (value "MMBT2222A")
      (footprint "eagle-import:TO-92-AMMO")
      (libsource (lib "eagle-import") (part "TRANSISTOR_NPNBC547"))
    )
    (comp (ref "Q5")
      (value "MMBT2222A")
      (footprint "eagle-import:TO-92-AMMO")
      (libsource (lib "eagle-import") (part "TRANSISTOR_NPNBC547"))
    )
    (comp (ref "Q6")
      (value "MMBT2222A")
      (footprint "eagle-import:TO-92-AMMO")
      (libsource (lib "eagle-import") (part "TRANSISTOR_NPNBC547"))
    )
    (comp (ref "R1")
      (value "MOV300V")
      (footprint "eagle-import:S10K11")
      (libsource (lib "eagle-import") (part "S10K11"))
    )
    (comp (ref "R2")
      (value "1K")
      (footprint "eagle-import:1206")
      (libsource (lib "eagle-import") (part "SparkFun-Resistors_RESISTOR1206"))
    )
    (comp (ref "R3")
      (value "1K")
      (footprint "eagle-import:1206")
      (libsource (lib "eagle-import") (part "RESISTOR1206"))
    )
    (comp (ref "R4")
      (value "1K")
      (footprint "eagle-import:1206")
      (libsource (lib "eagle-import") (part "SparkFun-Resistors_RESISTOR1206"))
    )
    (comp (ref "R5")
      (value "1K")
      (footprint "eagle-import:1206")
      (libsource (lib "eagle-import") (part "SparkFun-Resistors_RESISTOR1206"))
    )
    (comp (ref "R6")
      (value "10K")
      (footprint "eagle-import:1206")
      (libsource (lib "eagle-import") (part "RESISTOR1206"))
    )
    (comp (ref "R7")
      (value "4k7")
      (footprint "eagle-import:1206")
      (libsource (lib "eagle-import") (part "RESISTOR1206"))
    )
    (comp (ref "R8")
      (value "4k7")
      (footprint "eagle-import:1206")
      (libsource (lib "eagle-import") (part "RESISTOR1206"))
    )
    (comp (ref "R9")
      (value "1K")
      (footprint "eagle-import:1206")
      (libsource (lib "eagle-import") (part "SparkFun-Resistors_RESISTOR1206"))
    )
    (comp (ref "R10")
      (value "R-EU_0411/3V")
      (footprint "eagle-import:0411V")
      (libsource (lib "eagle-import") (part "R-EU_0411/3V"))
    )
    (comp (ref "R11")
      (value "S10K11")
      (footprint "eagle-import:S10K11")
      (libsource (lib "eagle-import") (part "S10K11"))
    )
    (comp (ref "R12")
      (value "1K")
      (footprint "eagle-import:1206")
      (libsource (lib "eagle-import") (part "SparkFun-Resistors_RESISTOR1206"))
    )
    (comp (ref "R13")
      (value "470R/0.5W")
      (footprint "eagle-import:0411V")
      (libsource (lib "eagle-import") (part "R-US_0411/3V"))
    )
    (comp (ref "R14")
      (value "10K")
      (footprint "eagle-import:1206")
      (libsource (lib "eagle-import") (part "RESISTOR1206"))
    )
    (comp (ref "R15")
      (value "560R")
      (footprint "eagle-import:1206")
      (libsource (lib "eagle-import") (part "SparkFun-Resistors_RESISTOR1206"))
    )
    (comp (ref "R16")
      (value "33k")
      (footprint "eagle-import:1206")
      (libsource (lib "eagle-import") (part "SparkFun-Resistors_RESISTOR1206"))
    )
    (comp (ref "R17")
      (value "33k")
      (footprint "eagle-import:0207_2V")
      (libsource (lib "eagle-import") (part "R-EU_0207/2V"))
    )
    (comp (ref "R21")
      (value "1K")
      (footprint "eagle-import:1206")
      (libsource (lib "eagle-import") (part "SparkFun-Resistors_RESISTOR1206"))
    )
    (comp (ref "R22")
      (value "1K")
      (footprint "eagle-import:1206")
      (libsource (lib "eagle-import") (part "SparkFun-Resistors_RESISTOR1206"))
    )
    (comp (ref "R23")
      (value "1K")
      (footprint "eagle-import:1206")
      (libsource (lib "eagle-import") (part "SparkFun-Resistors_RESISTOR1206"))
    )
    (comp (ref "R24")
      (value "1k")
      (footprint "eagle-import:0207_10")
      (libsource (lib "eagle-import") (part "R-EU_0207/10"))
    )
    (comp (ref "R25")
      (value "1k")
      (footprint "eagle-import:0207_10")
      (libsource (lib "eagle-import") (part "R-EU_0207/10"))
    )
    (comp (ref "R26")
      (value "1k")
      (footprint "eagle-import:0207_10")
      (libsource (lib "eagle-import") (part "R-EU_0207/10"))
    )
    (comp (ref "R27")
      (value "560R")
      (footprint "eagle-import:1206")
      (libsource (lib "eagle-import") (part "SparkFun-Resistors_RESISTOR1206"))
    )
    (comp (ref "R28")
      (value "470R/0.5W")
      (footprint "eagle-import:0411V")
      (libsource (lib "eagle-import") (part "R-US_0411/3V"))
    )
    (comp (ref "R29")
      (value "560R")
      (footprint "eagle-import:1206")
      (libsource (lib "eagle-import") (part "SparkFun-Resistors_RESISTOR1206"))
    )
    (comp (ref "R30")
      (value "470R/0.5W")
      (footprint "eagle-import:0411V")
      (libsource (lib "eagle-import") (part "R-US_0411/3V"))
    )
    (comp (ref "R31")
      (value "560R")
      (footprint "eagle-import:1206")
      (libsource (lib "eagle-import") (part "SparkFun-Resistors_RESISTOR1206"))
    )
    (comp (ref "R32")
      (value "470R/0.5W")
      (footprint "eagle-import:0411V")
      (libsource (lib "eagle-import") (part "R-US_0411/3V"))
    )
    (comp (ref "R33")
      (value "560R")
      (footprint "eagle-import:1206")
      (libsource (lib "eagle-import") (part "SparkFun-Resistors_RESISTOR1206"))
    )
    (comp (ref "R34")
      (value "470R/0.5W")
      (footprint "eagle-import:0411V")
      (libsource (lib "eagle-import") (part "R-US_0411/3V"))
    )
    (comp (ref "R35")
      (value "1k")
      (footprint "eagle-import:0207_10")
      (libsource (lib "eagle-import") (part "R-EU_0207/10"))
    )
    (comp (ref "RN1")
      (value "G07R")
      (footprint "eagle-import:SIL8")
      (libsource (lib "eagle-import") (part "G07R"))
    )
    (comp (ref "S1")
      (value "SWS008")
      (footprint "eagle-import:SMS-008")
      (libsource (lib "eagle-import") (part "SWS008"))
    )
    (comp (ref "T1")
      (value "BTB16-V")
      (footprint "eagle-import:TO220BV")
      (libsource (lib "eagle-import") (part "BT138-V"))
    )
    (comp (ref "T2")
      (value "BTB16-V")
      (footprint "eagle-import:TO220BV")
      (libsource (lib "eagle-import") (part "BT138-V"))
    )
    (comp (ref "T3")
      (value "BTB16-V")
      (footprint "eagle-import:TO220BV")
      (libsource (lib "eagle-import") (part "BT138-V"))
    )
    (comp (ref "T4")
      (value "BTB16-V")
      (footprint "eagle-import:TO220BV")
      (libsource (lib "eagle-import") (part "BT138-V"))
    )
    (comp (ref "U$1")
      (value "DS1307SO8")
      (footprint "eagle-import:SO08")
      (libsource (lib "eagle-import") (part "DS1307SO8"))
    )
    (comp (ref "U$2")
      (value "RF-LINK_RX")
      (footprint "eagle-import:RF-LINK_RX")
      (libsource (lib "eagle-import") (part "RF-LINK_RX"))
    )
    (comp (ref "U$3")
      (value "HM-11")
      (footprint "eagle-import:HM-11")
      (libsource (lib "eagle-import") (part "HM-11"))
    )
    (comp (ref "U$4")
      (value "220K")
      (footprint "eagle-import:1206")
      (libsource (lib "eagle-import") (part "SparkFun-Resistors_RESISTOR1206"))
    )
    (comp (ref "U$5")
      (value "2E2")
      (footprint "eagle-import:1206")
      (libsource (lib "eagle-import") (part "SparkFun-Resistors_RESISTOR1206"))
    )
    (comp (ref "U$6")
      (value "220K")
      (footprint "eagle-import:1206")
      (libsource (lib "eagle-import") (part "SparkFun-Resistors_RESISTOR1206"))
    )
    (comp (ref "U$7")
      (value "2E2")
      (footprint "eagle-import:1206")
      (libsource (lib "eagle-import") (part "SparkFun-Resistors_RESISTOR1206"))
    )
    (comp (ref "U$8")
      (value "220K")
      (footprint "eagle-import:1206")
      (libsource (lib "eagle-import") (part "SparkFun-Resistors_RESISTOR1206"))
    )
    (comp (ref "U$9")
      (value "2E2")
      (footprint "eagle-import:1206")
      (libsource (lib "eagle-import") (part "SparkFun-Resistors_RESISTOR1206"))
    )
    (comp (ref "U$11")
      (value "TEMPERATURE-SENSOR")
      (footprint "eagle-import:TO-92")
      (libsource (lib "eagle-import") (part "TEMPERATURE-SENSOR"))
    )
    (comp (ref "X1")
      (value "22-23-2051")
      (footprint "eagle-import:22-23-2051")
      (fields (field (name "MF") "MOLEX"))
      (libsource (lib "eagle-import") (part "22-23-2051"))
    )
    (comp (ref "X2")
      (value "22-23-2051")
      (footprint "eagle-import:22-23-2051")
      (fields (field (name "MF") "MOLEX"))
      (libsource (lib "eagle-import") (part "22-23-2051"))
    )
    (comp (ref "X3")
      (value "22-23-2051")
      (footprint "eagle-import:22-23-2051")
      (fields (field (name "MF") "MOLEX"))
      (libsource (lib "eagle-import") (part "22-23-2051"))
    )
    (comp (ref "X4")
      (value "AK300/4")
      (footprint "eagle-import:AK300_4")
      (libsource (lib "eagle-import") (part "AK300/4"))
    )
    (comp (ref "X5")
      (value "22-23-2041")
      (footprint "eagle-import:22-23-2041")
      (fields (field (name "MF") "MOLEX"))
      (libsource (lib "eagle-import") (part "22-23-2041"))
    )
    (comp (ref "X6")
      (value "22-23-2081")
      (footprint "eagle-import:22-23-2081")
      (fields (field (name "MF") "MOLEX"))
      (libsource (lib "eagle-import") (part "22-23-2081"))
    )
    (comp (ref "X7")
      (value "AK300/3")
      (footprint "eagle-import:AK300_3")
      (libsource (lib "eagle-import") (part "AK300/3"))
    )
    (comp (ref "X8")
      (value "AK300/2")
      (footprint "eagle-import:AK300_2")
      (libsource (lib "eagle-import") (part "AK300/2"))
    )
    (comp (ref "X9")
      (value "AK300/4")
      (footprint "eagle-import:AK300_4")
      (libsource (lib "eagle-import") (part "AK300/4"))
    )
    (comp (ref "X10")
      (value "AK300/4")
      (footprint "eagle-import:AK300_4")
      (libsource (lib "eagle-import") (part "AK300/4"))
    )
    (comp (ref "Y1")
      (value "32.768KHz")
      (footprint "eagle-import:TC26V")
      (libsource (lib "eagle-import") (part "CRYSTALTC26V"))
    )
  )
  (nets
    (net (code "1") (name "+3V3") (class "Default")
      (node (ref "C5") (pin "A") (pinfunction "+_A") (pintype "passive"))
      (node (ref "IC1") (pin "2") (pinfunction "OUT_2") (pintype "output"))
      (node (ref "IC1") (pin "4") (pinfunction "OUT_4") (pintype "output"))
      (node (ref "JP7") (pin "1") (pinfunction "1_1") (pintype "passive"))
      (node (ref "U$3") (pin "VCC") (pinfunction "VCC_VCC") (pintype "bidirectional"))
      (node (ref "X3") (pin "1") (pinfunction "S_1") (pintype "passive"))
    )
    (net (code "2") (name "+5V") (class "Default")
      (node (ref "ATMEGA32U4") (pin "14") (pinfunction "VCC_14") (pintype "bidirectional"))
      (node (ref "ATMEGA32U4") (pin "2") (pinfunction "UVCC_2") (pintype "bidirectional"))
      (node (ref "ATMEGA32U4") (pin "24") (pinfunction "AVCC_24") (pintype "bidirectional"))
      (node (ref "ATMEGA32U4") (pin "34") (pinfunction "VCC_34") (pintype "bidirectional"))
      (node (ref "ATMEGA32U4") (pin "44") (pinfunction "AVCC_44") (pintype "bidirectional"))
      (node (ref "ATMEGA32U4") (pin "7") (pinfunction "VBUS_7") (pintype "bidirectional"))
      (node (ref "C1") (pin "+") (pinfunction "+_+") (pintype "passive"))
      (node (ref "C18") (pin "1") (pinfunction "1_1") (pintype "passive"))
      (node (ref "C19") (pin "2") (pinfunction "2_2") (pintype "passive"))
      (node (ref "C3") (pin "1") (pinfunction "1_1") (pintype "passive"))
      (node (ref "C4") (pin "A") (pinfunction "+_A") (pintype "passive"))
      (node (ref "D1") (pin "C") (pinfunction "C_C") (pintype "passive"))
      (node (ref "D2") (pin "A") (pinfunction "A_A") (pintype "passive"))
      (node (ref "IC1") (pin "3") (pinfunction "IN_3") (pintype "input"))
      (node (ref "IC2") (pin "18") (pinfunction "VDD_18") (pintype "power_in"))
      (node (ref "JP1") (pin "1") (pinfunction "1_1") (pintype "passive"))
      (node (ref "LED3") (pin "A") (pinfunction "A_A") (pintype "passive"))
      (node (ref "R2") (pin "1") (pinfunction "1_1") (pintype "passive"))
      (node (ref "R6") (pin "2") (pinfunction "2_2") (pintype "passive"))
      (node (ref "RN1") (pin "1") (pinfunction "1_1") (pintype "passive"))
      (node (ref "U$11") (pin "3") (pinfunction "VCC_3") (pintype "bidirectional"))
      (node (ref "U$2") (pin "+5V@1") (pinfunction "+5V_+5V@1") (pintype "power_in"))
      (node (ref "X4") (pin "1") (pinfunction "KL_1") (pintype "passive"))
    )
    (net (code "3") (name "+12V") (class "Default")
      (node (ref "C10") (pin "+") (pinfunction "+_+") (pintype "passive"))
      (node (ref "C11") (pin "1") (pinfunction "1_1") (pintype "passive"))
      (node (ref "D10") (pin "A") (pinfunction "A_A") (pintype "passive"))
      (node (ref "D12") (pin "C") (pinfunction "C_C") (pintype "passive"))
      (node (ref "D4") (pin "A") (pinfunction "A_A") (pintype "passive"))
      (node (ref "D6") (pin "A") (pinfunction "A_A") (pintype "passive"))
      (node (ref "D8") (pin "A") (pinfunction "A_A") (pintype "passive"))
      (node (ref "K1") (pin "1") (pinfunction "1_1") (pintype "passive"))
      (node (ref "K2") (pin "1") (pinfunction "1_1") (pintype "passive"))
      (node (ref "K3") (pin "1") (pinfunction "1_1") (pintype "passive"))
      (node (ref "K4") (pin "1") (pinfunction "1_1") (pintype "passive"))
      (node (ref "OK1") (pin "4") (pinfunction "COL_4") (pintype "passive"))
      (node (ref "OK2") (pin "4") (pinfunction "COL_4") (pintype "passive"))
      (node (ref "OK3") (pin "4") (pinfunction "COL_4") (pintype "passive"))
      (node (ref "OK8") (pin "4") (pinfunction "COL_4") (pintype "passive"))
      (node (ref "R12") (pin "1") (pinfunction "1_1") (pintype "passive"))
      (node (ref "R21") (pin "2") (pinfunction "2_2") (pintype "passive"))
      (node (ref "R22") (pin "2") (pinfunction "2_2") (pintype "passive"))
      (node (ref "R23") (pin "2") (pinfunction "2_2") (pintype "passive"))
      (node (ref "R9") (pin "2") (pinfunction "2_2") (pintype "passive"))
      (node (ref "X4") (pin "3") (pinfunction "KL_3") (pintype "passive"))
    )
    (net (code "4") (name "/(DIN)TE") (class "Default")
      (node (ref "IC2") (pin "14") (pinfunction "A6_14") (pintype "input"))
      (node (ref "U$2") (pin "DATA@1") (pinfunction "DATA_DATA@1") (pintype "input"))
    )
    (net (code "5") (name "/(VT)ADOUT") (class "Default")
      (node (ref "IC2") (pin "17") (pinfunction "A9_17") (pintype "input"))
      (node (ref "R14") (pin "2") (pinfunction "2_2") (pintype "passive"))
    )
    (net (code "6") (name "/25") (class "Default")
      (node (ref "ATMEGA32U4") (pin "25") (pinfunction "PD4(ADC8)_25") (pintype "bidirectional"))
      (node (ref "JP6") (pin "1") (pinfunction "1_1") (pintype "passive"))
    )
    (net (code "7") (name "/26") (class "Default")
      (node (ref "ATMEGA32U4") (pin "26") (pinfunction "PD6(ADC9)_26") (pintype "bidirectional"))
      (node (ref "JP6") (pin "2") (pinfunction "2_2") (pintype "passive"))
    )
    (net (code "8") (name "/27") (class "Default")
      (node (ref "ATMEGA32U4") (pin "27") (pinfunction "PD7(ADC10)_27") (pintype "bidirectional"))
      (node (ref "JP6") (pin "3") (pinfunction "3_3") (pintype "passive"))
    )
    (net (code "9") (name "/28") (class "Default")
      (node (ref "ATMEGA32U4") (pin "28") (pinfunction "PB4(ADC11)_28") (pintype "bidirectional"))
      (node (ref "JP6") (pin "4") (pinfunction "4_4") (pintype "passive"))
    )
    (net (code "10") (name "/29") (class "Default")
      (node (ref "ATMEGA32U4") (pin "29") (pinfunction "PB5(ADC12)_29") (pintype "bidirectional"))
      (node (ref "JP6") (pin "5") (pinfunction "5_5") (pintype "passive"))
    )
    (net (code "11") (name "/30") (class "Default")
      (node (ref "ATMEGA32U4") (pin "30") (pinfunction "PB6(ADC13)_30") (pintype "bidirectional"))
      (node (ref "JP6") (pin "6") (pinfunction "6_6") (pintype "passive"))
    )
    (net (code "12") (name "/31") (class "Default")
      (node (ref "ATMEGA32U4") (pin "31") (pinfunction "PC6_31") (pintype "bidirectional"))
      (node (ref "JP6") (pin "7") (pinfunction "7_7") (pintype "passive"))
    )
    (net (code "13") (name "/32") (class "Default")
      (node (ref "ATMEGA32U4") (pin "32") (pinfunction "PC7_32") (pintype "bidirectional"))
      (node (ref "JP6") (pin "8") (pinfunction "8_8") (pintype "passive"))
    )
    (net (code "14") (name "/A0") (class "Default")
      (node (ref "IC2") (pin "1") (pinfunction "AD11_1") (pintype "input"))
      (node (ref "S1") (pin "16") (pinfunction "16_16") (pintype "passive"))
    )
    (net (code "15") (name "/A1") (class "Default")
      (node (ref "IC2") (pin "2") (pinfunction "AD12_2") (pintype "input"))
      (node (ref "S1") (pin "15") (pinfunction "15_15") (pintype "passive"))
    )
    (net (code "16") (name "/A2") (class "Default")
      (node (ref "IC2") (pin "3") (pinfunction "AD14_3") (pintype "input"))
      (node (ref "S1") (pin "14") (pinfunction "14_14") (pintype "passive"))
    )
    (net (code "17") (name "/A3") (class "Default")
      (node (ref "IC2") (pin "4") (pinfunction "AD15_4") (pintype "input"))
      (node (ref "S1") (pin "13") (pinfunction "13_13") (pintype "passive"))
    )
    (net (code "18") (name "/A4") (class "Default")
      (node (ref "IC2") (pin "5") (pinfunction "DOUT_5") (pintype "input"))
      (node (ref "S1") (pin "12") (pinfunction "12_12") (pintype "passive"))
    )
    (net (code "19") (name "/A5") (class "Default")
      (node (ref "IC2") (pin "6") (pinfunction "TE_6") (pintype "input"))
      (node (ref "S1") (pin "11") (pinfunction "11_11") (pintype "passive"))
    )
    (net (code "20") (name "/A6") (class "Default")
      (node (ref "IC2") (pin "7") (pinfunction "OSC2_7") (pintype "output"))
      (node (ref "S1") (pin "10") (pinfunction "10_10") (pintype "passive"))
    )
    (net (code "21") (name "/A7") (class "Default")
      (node (ref "IC2") (pin "8") (pinfunction "OSC1_8") (pintype "input"))
      (node (ref "S1") (pin "9") (pinfunction "9_9") (pintype "passive"))
    )
    (net (code "22") (name "/BLE_STATUS") (class "Default")
      (node (ref "R3") (pin "2") (pinfunction "2_2") (pintype "passive"))
      (node (ref "U$3") (pin "PIO1") (pinfunction "PIO1_PIO1") (pintype "bidirectional"))
    )
    (net (code "23") (name "/D8") (class "Default")
      (node (ref "IC2") (pin "10") (pinfunction "A0_10") (pintype "input"))
      (node (ref "X5") (pin "4") (pinfunction "S_4") (pintype "passive"))
    )
    (net (code "24") (name "/D9") (class "Default")
      (node (ref "IC2") (pin "11") (pinfunction "A1_11") (pintype "input"))
      (node (ref "X5") (pin "3") (pinfunction "S_3") (pintype "passive"))
    )
    (net (code "25") (name "/D10") (class "Default")
      (node (ref "IC2") (pin "12") (pinfunction "A2_12") (pintype "input"))
      (node (ref "X5") (pin "2") (pinfunction "S_2") (pintype "passive"))
    )
    (net (code "26") (name "/D11") (class "Default")
      (node (ref "IC2") (pin "13") (pinfunction "A3_13") (pintype "input"))
      (node (ref "X5") (pin "1") (pinfunction "S_1") (pintype "passive"))
    )
    (net (code "27") (name "/DOWN") (class "Default")
      (node (ref "CN2") (pin "7") (pinfunction "S_7") (pintype "passive"))
      (node (ref "RN1") (pin "7") (pinfunction "7_7") (pintype "passive"))
      (node (ref "X6") (pin "7") (pinfunction "S_7") (pintype "passive"))
    )
    (net (code "28") (name "/FAN_ON{slash}OFF") (class "Default")
      (node (ref "CN2") (pin "8") (pinfunction "S_8") (pintype "passive"))
      (node (ref "RN1") (pin "8") (pinfunction "8_8") (pintype "passive"))
      (node (ref "X6") (pin "8") (pinfunction "S_8") (pintype "passive"))
    )
    (net (code "29") (name "/FAN_REG") (class "Default")
      (node (ref "C2") (pin "-") (pinfunction "-_-") (pintype "passive"))
      (node (ref "R11") (pin "1") (pinfunction "1_1") (pintype "passive"))
      (node (ref "T4") (pin "T1") (pinfunction "A1_T1") (pintype "passive"))
      (node (ref "U$5") (pin "1") (pinfunction "1_1") (pintype "passive"))
      (node (ref "U$7") (pin "1") (pinfunction "1_1") (pintype "passive"))
      (node (ref "U$9") (pin "1") (pinfunction "1_1") (pintype "passive"))
      (node (ref "X8") (pin "1") (pinfunction "KL_1") (pintype "passive"))
    )
    (net (code "30") (name "/LINE") (class "Default")
      (node (ref "F1") (pin "1") (pinfunction "1_1") (pintype "passive"))
      (node (ref "K1") (pin "C") (pinfunction "P_C") (pintype "passive"))
      (node (ref "K2") (pin "C") (pinfunction "P_C") (pintype "passive"))
      (node (ref "K3") (pin "C") (pinfunction "P_C") (pintype "passive"))
      (node (ref "K4") (pin "C") (pinfunction "P_C") (pintype "passive"))
      (node (ref "R1") (pin "2") (pinfunction "2_2") (pintype "passive"))
      (node (ref "R10") (pin "2") (pinfunction "2_2") (pintype "passive"))
      (node (ref "R11") (pin "2") (pinfunction "2_2") (pintype "passive"))
      (node (ref "R28") (pin "2") (pinfunction "2_2") (pintype "passive"))
      (node (ref "R30") (pin "2") (pinfunction "2_2") (pintype "passive"))
      (node (ref "R32") (pin "2") (pinfunction "2_2") (pintype "passive"))
      (node (ref "R34") (pin "2") (pinfunction "2_2") (pintype "passive"))
      (node (ref "T1") (pin "T2") (pinfunction "A2_T2") (pintype "passive"))
      (node (ref "T2") (pin "T2") (pinfunction "A2_T2") (pintype "passive"))
      (node (ref "T3") (pin "T2") (pinfunction "A2_T2") (pintype "passive"))
      (node (ref "T4") (pin "T2") (pinfunction "A2_T2") (pintype "passive"))
    )
    (net (code "31") (name "/MISO") (class "Default")
      (node (ref "ATMEGA32U4") (pin "11") (pinfunction "PB3(MISO)_11") (pintype "bidirectional"))
      (node (ref "JP3") (pin "4") (pinfunction "4_4") (pintype "passive"))
    )
    (net (code "32") (name "/MOSI") (class "Default")
      (node (ref "ATMEGA32U4") (pin "10") (pinfunction "PB2(MOSI)_10") (pintype "bidirectional"))
      (node (ref "JP1") (pin "4") (pinfunction "4_4") (pintype "passive"))
      (node (ref "JP3") (pin "3") (pinfunction "3_3") (pintype "passive"))
    )
    (net (code "33") (name "/N$74") (class "Default")
      (node (ref "ATMEGA32U4") (pin "8") (pinfunction "PB0(SS)_8") (pintype "bidirectional"))
      (node (ref "JP3") (pin "1") (pinfunction "1_1") (pintype "passive"))
    )
    (net (code "34") (name "/NEUTRAL") (class "Default")
      (node (ref "R1") (pin "1") (pinfunction "1_1") (pintype "passive"))
      (node (ref "X7") (pin "2") (pinfunction "KL_2") (pintype "passive"))
      (node (ref "X7") (pin "3") (pinfunction "KL_3") (pintype "passive"))
      (node (ref "X8") (pin "2") (pinfunction "KL_2") (pintype "passive"))
      (node (ref "X9") (pin "1") (pinfunction "KL_1") (pintype "passive"))
      (node (ref "X9") (pin "2") (pinfunction "KL_2") (pintype "passive"))
      (node (ref "X9") (pin "3") (pinfunction "KL_3") (pintype "passive"))
      (node (ref "X9") (pin "4") (pinfunction "KL_4") (pintype "passive"))
    )
    (net (code "35") (name "/OSC1") (class "Default")
      (node (ref "IC2") (pin "16") (pinfunction "A8_16") (pintype "input"))
      (node (ref "R16") (pin "1") (pinfunction "1_1") (pintype "passive"))
      (node (ref "R17") (pin "1") (pinfunction "1_1") (pintype "passive"))
    )
    (net (code "36") (name "/OSC2") (class "Default")
      (node (ref "IC2") (pin "15") (pinfunction "A7_15") (pintype "input"))
      (node (ref "R16") (pin "2") (pinfunction "2_2") (pintype "passive"))
      (node (ref "R17") (pin "2") (pinfunction "2_2") (pintype "passive"))
    )
    (net (code "37") (name "/RX") (class "Default")
      (node (ref "ATMEGA32U4") (pin "21") (pinfunction "PD3(TX)_21") (pintype "bidirectional"))
      (node (ref "JP4") (pin "4") (pinfunction "4_4") (pintype "passive"))
      (node (ref "JP7") (pin "3") (pinfunction "3_3") (pintype "passive"))
      (node (ref "R5") (pin "1") (pinfunction "1_1") (pintype "passive"))
      (node (ref "X3") (pin "3") (pinfunction "S_3") (pintype "passive"))
    )
    (net (code "38") (name "/SCK") (class "Default")
      (node (ref "ATMEGA32U4") (pin "9") (pinfunction "PB1(SCK)_9") (pintype "bidirectional"))
      (node (ref "JP1") (pin "5") (pinfunction "5_5") (pintype "passive"))
      (node (ref "JP3") (pin "2") (pinfunction "2_2") (pintype "passive"))
    )
    (net (code "39") (name "/SCL") (class "Default")
      (node (ref "ATMEGA32U4") (pin "18") (pinfunction "PD0(SCL)_18") (pintype "bidirectional"))
      (node (ref "JP4") (pin "1") (pinfunction "1_1") (pintype "passive"))
      (node (ref "JP9") (pin "1") (pinfunction "1_1") (pintype "passive"))
      (node (ref "R7") (pin "2") (pinfunction "2_2") (pintype "passive"))
      (node (ref "U$1") (pin "6") (pinfunction "SCL_6") (pintype "bidirectional"))
    )
    (net (code "40") (name "/SDA") (class "Default")
      (node (ref "ATMEGA32U4") (pin "19") (pinfunction "PD1(SDA)_19") (pintype "bidirectional"))
      (node (ref "JP4") (pin "2") (pinfunction "2_2") (pintype "passive"))
      (node (ref "JP9") (pin "2") (pinfunction "2_2") (pintype "passive"))
      (node (ref "R8") (pin "2") (pinfunction "2_2") (pintype "passive"))
      (node (ref "U$1") (pin "5") (pinfunction "SDA_5") (pintype "bidirectional"))
    )
    (net (code "41") (name "/SW-1") (class "Default")
      (node (ref "CN2") (pin "2") (pinfunction "S_2") (pintype "passive"))
      (node (ref "RN1") (pin "2") (pinfunction "2_2") (pintype "passive"))
      (node (ref "X6") (pin "2") (pinfunction "S_2") (pintype "passive"))
    )
    (net (code "42") (name "/SW-2") (class "Default")
      (node (ref "CN2") (pin "3") (pinfunction "S_3") (pintype "passive"))
      (node (ref "RN1") (pin "3") (pinfunction "3_3") (pintype "passive"))
      (node (ref "X6") (pin "3") (pinfunction "S_3") (pintype "passive"))
    )
    (net (code "43") (name "/SW-3") (class "Default")
      (node (ref "CN2") (pin "4") (pinfunction "S_4") (pintype "passive"))
      (node (ref "RN1") (pin "4") (pinfunction "4_4") (pintype "passive"))
      (node (ref "X6") (pin "4") (pinfunction "S_4") (pintype "passive"))
    )
    (net (code "44") (name "/SW-4") (class "Default")
      (node (ref "CN2") (pin "5") (pinfunction "S_5") (pintype "passive"))
      (node (ref "RN1") (pin "5") (pinfunction "5_5") (pintype "passive"))
      (node (ref "X6") (pin "5") (pinfunction "S_5") (pintype "passive"))
    )
    (net (code "45") (name "/TX") (class "Default")
      (node (ref "ATMEGA32U4") (pin "20") (pinfunction "PD2(RX)_20") (pintype "bidirectional"))
      (node (ref "JP4") (pin "3") (pinfunction "3_3") (pintype "passive"))
      (node (ref "JP7") (pin "4") (pinfunction "4_4") (pintype "passive"))
      (node (ref "R4") (pin "1") (pinfunction "1_1") (pintype "passive"))
      (node (ref "X3") (pin "4") (pinfunction "S_4") (pintype "passive"))
    )
    (net (code "46") (name "/UP") (class "Default")
      (node (ref "CN2") (pin "6") (pinfunction "S_6") (pintype "passive"))
      (node (ref "RN1") (pin "6") (pinfunction "6_6") (pintype "passive"))
      (node (ref "X6") (pin "6") (pinfunction "S_6") (pintype "passive"))
    )
    (net (code "47") (name "/~{RESET}") (class "Default")
      (node (ref "ATMEGA32U4") (pin "13") (pinfunction "~{RESET}_13") (pintype "bidirectional"))
      (node (ref "JP1") (pin "3") (pinfunction "3_3") (pintype "passive"))
      (node (ref "JP7") (pin "5") (pinfunction "5_5") (pintype "passive"))
      (node (ref "R6") (pin "1") (pinfunction "1_1") (pintype "passive"))
      (node (ref "U$3") (pin "UART_RTS") (pinfunction "UART_RTS_UART_RTS") (pintype "bidirectional"))
      (node (ref "X3") (pin "5") (pinfunction "S_5") (pintype "passive"))
    )
    (net (code "48") (name "GND") (class "Default")
      (node (ref "ATMEGA32U4") (pin "15") (pinfunction "GND_15") (pintype "bidirectional"))
      (node (ref "ATMEGA32U4") (pin "23") (pinfunction "GND_23") (pintype "bidirectional"))
      (node (ref "ATMEGA32U4") (pin "33") (pinfunction "PE2/~{HWB}_33") (pintype "bidirectional"))
      (node (ref "ATMEGA32U4") (pin "35") (pinfunction "GND_35") (pintype "bidirectional"))
      (node (ref "ATMEGA32U4") (pin "43") (pinfunction "GND_43") (pintype "bidirectional"))
      (node (ref "ATMEGA32U4") (pin "5") (pinfunction "UGND_5") (pintype "bidirectional"))
      (node (ref "B1") (pin "-") (pinfunction "-_-") (pintype "passive"))
      (node (ref "C1") (pin "-") (pinfunction "-_-") (pintype "passive"))
      (node (ref "C18") (pin "2") (pinfunction "2_2") (pintype "passive"))
      (node (ref "C19") (pin "1") (pinfunction "1_1") (pintype "passive"))
      (node (ref "C3") (pin "2") (pinfunction "2_2") (pintype "passive"))
      (node (ref "C4") (pin "C") (pinfunction "-_C") (pintype "passive"))
      (node (ref "C5") (pin "C") (pinfunction "-_C") (pintype "passive"))
      (node (ref "C6") (pin "2") (pinfunction "2_2") (pintype "passive"))
      (node (ref "C7") (pin "1") (pinfunction "1_1") (pintype "passive"))
      (node (ref "C8") (pin "1") (pinfunction "1_1") (pintype "passive"))
      (node (ref "C9") (pin "1") (pinfunction "1_1") (pintype "passive"))
      (node (ref "CN2") (pin "1") (pinfunction "S_1") (pintype "passive"))
      (node (ref "D1") (pin "A") (pinfunction "A_A") (pintype "passive"))
      (node (ref "IC1") (pin "1") (pinfunction "ADJ_1") (pintype "input"))
      (node (ref "IC2") (pin "9") (pinfunction "VSS_9") (pintype "power_in"))
      (node (ref "JP1") (pin "2") (pinfunction "2_2") (pintype "passive"))
      (node (ref "JP7") (pin "2") (pinfunction "2_2") (pintype "passive"))
      (node (ref "LED1") (pin "K") (pinfunction "C_K") (pintype "passive"))
      (node (ref "LED2") (pin "C") (pinfunction "C_C") (pintype "passive"))
      (node (ref "OK1") (pin "2") (pinfunction "C_2") (pintype "passive"))
      (node (ref "OK2") (pin "2") (pinfunction "C_2") (pintype "passive"))
      (node (ref "OK3") (pin "2") (pinfunction "C_2") (pintype "passive"))
      (node (ref "OK4") (pin "2") (pinfunction "C_2") (pintype "passive"))
      (node (ref "OK5") (pin "2") (pinfunction "C_2") (pintype "passive"))
      (node (ref "OK6") (pin "2") (pinfunction "C_2") (pintype "passive"))
      (node (ref "OK7") (pin "2") (pinfunction "C_2") (pintype "passive"))
      (node (ref "OK8") (pin "2") (pinfunction "C_2") (pintype "passive"))
      (node (ref "Q2") (pin "2") (pinfunction "E_2") (pintype "passive"))
      (node (ref "S1") (pin "1") (pinfunction "1_1") (pintype "passive"))
      (node (ref "S1") (pin "2") (pinfunction "2_2") (pintype "passive"))
      (node (ref "S1") (pin "3") (pinfunction "3_3") (pintype "passive"))
      (node (ref "S1") (pin "4") (pinfunction "4_4") (pintype "passive"))
      (node (ref "S1") (pin "5") (pinfunction "5_5") (pintype "passive"))
      (node (ref "S1") (pin "6") (pinfunction "6_6") (pintype "passive"))
      (node (ref "S1") (pin "7") (pinfunction "7_7") (pintype "passive"))
      (node (ref "S1") (pin "8") (pinfunction "8_8") (pintype "passive"))
      (node (ref "U$1") (pin "4") (pinfunction "GND_4") (pintype "bidirectional"))
      (node (ref "U$11") (pin "1") (pinfunction "GND_1") (pintype "bidirectional"))
      (node (ref "U$2") (pin "GND@1") (pinfunction "GND_GND@1") (pintype "power_in"))
      (node (ref "U$3") (pin "GND") (pinfunction "GND_GND") (pintype "bidirectional"))
      (node (ref "X1") (pin "5") (pinfunction "S_5") (pintype "passive"))
      (node (ref "X2") (pin "5") (pinfunction "S_5") (pintype "passive"))
      (node (ref "X3") (pin "2") (pinfunction "S_2") (pintype "passive"))
      (node (ref "X4") (pin "2") (pinfunction "KL_2") (pintype "passive"))
    )
    (net (code "49") (name "GNDA") (class "Default")
      (node (ref "C10") (pin "-") (pinfunction "-_-") (pintype "passive"))
      (node (ref "C11") (pin "2") (pinfunction "2_2") (pintype "passive"))
      (node (ref "D12") (pin "A") (pinfunction "A_A") (pintype "passive"))
      (node (ref "LED8") (pin "K") (pinfunction "C_K") (pintype "passive"))
      (node (ref "Q3") (pin "3") (pinfunction "E_3") (pintype "passive"))
      (node (ref "Q4") (pin "3") (pinfunction "E_3") (pintype "passive"))
      (node (ref "Q5") (pin "3") (pinfunction "E_3") (pintype "passive"))
      (node (ref "Q6") (pin "3") (pinfunction "E_3") (pintype "passive"))
      (node (ref "X4") (pin "4") (pinfunction "KL_4") (pintype "passive"))
    )
    (net (code "50") (name "Net-(ANT1-Pad1)") (class "Default")
      (node (ref "ANT1") (pin "1") (pinfunction "1_1") (pintype "output"))
      (node (ref "U$2") (pin "ANT") (pinfunction "ANT_ANT") (pintype "passive"))
    )
    (net (code "51") (name "Net-(ATMEGA32U4-AREF)") (class "Default")
      (node (ref "ATMEGA32U4") (pin "42") (pinfunction "AREF_42") (pintype "bidirectional"))
      (node (ref "C6") (pin "1") (pinfunction "1_1") (pintype "passive"))
    )
    (net (code "52") (name "Net-(ATMEGA32U4-PB7)") (class "Default")
      (node (ref "ATMEGA32U4") (pin "12") (pinfunction "PB7_12") (pintype "bidirectional"))
      (node (ref "JP3") (pin "5") (pinfunction "5_5") (pintype "passive"))
    )
    (net (code "53") (name "Net-(ATMEGA32U4-PD5)") (class "Default")
      (node (ref "ATMEGA32U4") (pin "22") (pinfunction "PD5_22") (pintype "bidirectional"))
      (node (ref "JP4") (pin "5") (pinfunction "5_5") (pintype "passive"))
    )
    (net (code "54") (name "Net-(ATMEGA32U4-PE6)") (class "Default")
      (node (ref "ATMEGA32U4") (pin "1") (pinfunction "PE6_1") (pintype "bidirectional"))
      (node (ref "JP5") (pin "1") (pinfunction "1_1") (pintype "passive"))
    )
    (net (code "55") (name "Net-(ATMEGA32U4-PF0(ADC0))") (class "Default")
      (node (ref "ATMEGA32U4") (pin "41") (pinfunction "PF0(ADC0)_41") (pintype "bidirectional"))
      (node (ref "JP2") (pin "6") (pinfunction "6_6") (pintype "passive"))
    )
    (net (code "56") (name "Net-(ATMEGA32U4-PF1(ADC1))") (class "Default")
      (node (ref "ATMEGA32U4") (pin "40") (pinfunction "PF1(ADC1)_40") (pintype "bidirectional"))
      (node (ref "JP2") (pin "5") (pinfunction "5_5") (pintype "passive"))
    )
    (net (code "57") (name "Net-(ATMEGA32U4-PF4(ADC4))") (class "Default")
      (node (ref "ATMEGA32U4") (pin "39") (pinfunction "PF4(ADC4)_39") (pintype "bidirectional"))
      (node (ref "JP2") (pin "4") (pinfunction "4_4") (pintype "passive"))
    )
    (net (code "58") (name "Net-(ATMEGA32U4-PF5(ADC5))") (class "Default")
      (node (ref "ATMEGA32U4") (pin "38") (pinfunction "PF5(ADC5)_38") (pintype "bidirectional"))
      (node (ref "JP2") (pin "3") (pinfunction "3_3") (pintype "passive"))
    )
    (net (code "59") (name "Net-(ATMEGA32U4-PF6(ADC6))") (class "Default")
      (node (ref "ATMEGA32U4") (pin "37") (pinfunction "PF6(ADC6)_37") (pintype "bidirectional"))
      (node (ref "JP2") (pin "2") (pinfunction "2_2") (pintype "passive"))
    )
    (net (code "60") (name "Net-(ATMEGA32U4-PF7(ADC7))") (class "Default")
      (node (ref "ATMEGA32U4") (pin "36") (pinfunction "PF7(ADC7)_36") (pintype "bidirectional"))
      (node (ref "JP2") (pin "1") (pinfunction "1_1") (pintype "passive"))
    )
    (net (code "61") (name "Net-(ATMEGA32U4-UCAP)") (class "Default")
      (node (ref "ATMEGA32U4") (pin "6") (pinfunction "UCAP_6") (pintype "bidirectional"))
      (node (ref "C7") (pin "2") (pinfunction "2_2") (pintype "passive"))
    )
    (net (code "62") (name "Net-(ATMEGA32U4-XTAL1)") (class "Default")
      (node (ref "ATMEGA32U4") (pin "17") (pinfunction "XTAL1_17") (pintype "bidirectional"))
      (node (ref "C9") (pin "2") (pinfunction "2_2") (pintype "passive"))
      (node (ref "Q1") (pin "1") (pinfunction "1_1") (pintype "passive"))
    )
    (net (code "63") (name "Net-(ATMEGA32U4-XTAL2)") (class "Default")
      (node (ref "ATMEGA32U4") (pin "16") (pinfunction "XTAL2_16") (pintype "bidirectional"))
      (node (ref "C8") (pin "2") (pinfunction "2_2") (pintype "passive"))
      (node (ref "Q1") (pin "2") (pinfunction "2_2") (pintype "passive"))
    )
    (net (code "64") (name "Net-(B1-Pad+)") (class "Default")
      (node (ref "B1") (pin "+") (pinfunction "+_+") (pintype "passive"))
      (node (ref "D3") (pin "A") (pinfunction "A_A") (pintype "passive"))
    )
    (net (code "65") (name "Net-(C2-Pad+)") (class "Default")
      (node (ref "C2") (pin "+") (pinfunction "+_+") (pintype "passive"))
      (node (ref "R10") (pin "1") (pinfunction "1_1") (pintype "passive"))
    )
    (net (code "66") (name "Net-(C14-Pad2)") (class "Default")
      (node (ref "C14") (pin "2") (pinfunction "2_2") (pintype "passive"))
      (node (ref "U$4") (pin "1") (pinfunction "1_1") (pintype "passive"))
      (node (ref "U$5") (pin "2") (pinfunction "2_2") (pintype "passive"))
    )
    (net (code "67") (name "Net-(C15-Pad2)") (class "Default")
      (node (ref "C15") (pin "2") (pinfunction "2_2") (pintype "passive"))
      (node (ref "U$6") (pin "1") (pinfunction "1_1") (pintype "passive"))
      (node (ref "U$7") (pin "2") (pinfunction "2_2") (pintype "passive"))
    )
    (net (code "68") (name "Net-(C16-Pad2)") (class "Default")
      (node (ref "C16") (pin "2") (pinfunction "2_2") (pintype "passive"))
      (node (ref "C17") (pin "2") (pinfunction "2_2") (pintype "passive"))
      (node (ref "U$8") (pin "1") (pinfunction "1_1") (pintype "passive"))
      (node (ref "U$9") (pin "2") (pinfunction "2_2") (pintype "passive"))
    )
    (net (code "69") (name "Net-(D4-PadC)") (class "Default")
      (node (ref "D4") (pin "C") (pinfunction "C_C") (pintype "passive"))
      (node (ref "D5") (pin "C") (pinfunction "C_C") (pintype "passive"))
    )
    (net (code "70") (name "Net-(D6-PadC)") (class "Default")
      (node (ref "D6") (pin "C") (pinfunction "C_C") (pintype "passive"))
      (node (ref "D7") (pin "C") (pinfunction "C_C") (pintype "passive"))
    )
    (net (code "71") (name "Net-(D8-PadC)") (class "Default")
      (node (ref "D8") (pin "C") (pinfunction "C_C") (pintype "passive"))
      (node (ref "D9") (pin "C") (pinfunction "C_C") (pintype "passive"))
    )
    (net (code "72") (name "Net-(D10-PadC)") (class "Default")
      (node (ref "D10") (pin "C") (pinfunction "C_C") (pintype "passive"))
      (node (ref "D11") (pin "C") (pinfunction "C_C") (pintype "passive"))
    )
    (net (code "73") (name "Net-(K1B-S)") (class "Default")
      (node (ref "K1") (pin "NO") (pinfunction "S_NO") (pintype "passive"))
      (node (ref "X10") (pin "1") (pinfunction "KL_1") (pintype "passive"))
    )
    (net (code "74") (name "Net-(K2B-S)") (class "Default")
      (node (ref "K2") (pin "NO") (pinfunction "S_NO") (pintype "passive"))
      (node (ref "X10") (pin "2") (pinfunction "KL_2") (pintype "passive"))
    )
    (net (code "75") (name "Net-(K3B-S)") (class "Default")
      (node (ref "K3") (pin "NO") (pinfunction "S_NO") (pintype "passive"))
      (node (ref "X10") (pin "3") (pinfunction "KL_3") (pintype "passive"))
    )
    (net (code "76") (name "Net-(K4B-S)") (class "Default")
      (node (ref "K4") (pin "NO") (pinfunction "S_NO") (pintype "passive"))
      (node (ref "X10") (pin "4") (pinfunction "KL_4") (pintype "passive"))
    )
    (net (code "77") (name "Net-(LED1-PadA)") (class "Default")
      (node (ref "LED1") (pin "A") (pinfunction "A_A") (pintype "passive"))
      (node (ref "R2") (pin "2") (pinfunction "2_2") (pintype "passive"))
    )
    (net (code "78") (name "Net-(LED2-PadA)") (class "Default")
      (node (ref "LED2") (pin "A") (pinfunction "A_A") (pintype "passive"))
      (node (ref "R3") (pin "1") (pinfunction "1_1") (pintype "passive"))
    )
    (net (code "79") (name "Net-(LED3-C)") (class "Default")
      (node (ref "LED3") (pin "K") (pinfunction "C_K") (pintype "passive"))
      (node (ref "R15") (pin "2") (pinfunction "2_2") (pintype "passive"))
    )
    (net (code "80") (name "Net-(LED4-C)") (class "Default")
      (node (ref "D5") (pin "A") (pinfunction "A_A") (pintype "passive"))
      (node (ref "K1") (pin "2") (pinfunction "2_2") (pintype "passive"))
      (node (ref "LED4") (pin "K") (pinfunction "C_K") (pintype "passive"))
      (node (ref "Q3") (pin "1") (pinfunction "C_1") (pintype "passive"))
    )
    (net (code "81") (name "Net-(LED4-PadA)") (class "Default")
      (node (ref "LED4") (pin "A") (pinfunction "A_A") (pintype "passive"))
      (node (ref "R9") (pin "1") (pinfunction "1_1") (pintype "passive"))
    )
    (net (code "82") (name "Net-(LED5-C)") (class "Default")
      (node (ref "D7") (pin "A") (pinfunction "A_A") (pintype "passive"))
      (node (ref "K2") (pin "2") (pinfunction "2_2") (pintype "passive"))
      (node (ref "LED5") (pin "K") (pinfunction "C_K") (pintype "passive"))
      (node (ref "Q4") (pin "1") (pinfunction "C_1") (pintype "passive"))
    )
    (net (code "83") (name "Net-(LED5-PadA)") (class "Default")
      (node (ref "LED5") (pin "A") (pinfunction "A_A") (pintype "passive"))
      (node (ref "R21") (pin "1") (pinfunction "1_1") (pintype "passive"))
    )
    (net (code "84") (name "Net-(LED6-C)") (class "Default")
      (node (ref "D9") (pin "A") (pinfunction "A_A") (pintype "passive"))
      (node (ref "K3") (pin "2") (pinfunction "2_2") (pintype "passive"))
      (node (ref "LED6") (pin "K") (pinfunction "C_K") (pintype "passive"))
      (node (ref "Q5") (pin "1") (pinfunction "C_1") (pintype "passive"))
    )
    (net (code "85") (name "Net-(LED6-PadA)") (class "Default")
      (node (ref "LED6") (pin "A") (pinfunction "A_A") (pintype "passive"))
      (node (ref "R22") (pin "1") (pinfunction "1_1") (pintype "passive"))
    )
    (net (code "86") (name "Net-(LED7-C)") (class "Default")
      (node (ref "D11") (pin "A") (pinfunction "A_A") (pintype "passive"))
      (node (ref "K4") (pin "2") (pinfunction "2_2") (pintype "passive"))
      (node (ref "LED7") (pin "K") (pinfunction "C_K") (pintype "passive"))
      (node (ref "Q6") (pin "1") (pinfunction "C_1") (pintype "passive"))
    )
    (net (code "87") (name "Net-(LED7-PadA)") (class "Default")
      (node (ref "LED7") (pin "A") (pinfunction "A_A") (pintype "passive"))
      (node (ref "R23") (pin "1") (pinfunction "1_1") (pintype "passive"))
    )
    (net (code "88") (name "Net-(LED8-PadA)") (class "Default")
      (node (ref "LED8") (pin "A") (pinfunction "A_A") (pintype "passive"))
      (node (ref "R12") (pin "2") (pinfunction "2_2") (pintype "passive"))
    )
    (net (code "89") (name "Net-(OK1-A)") (class "Default")
      (node (ref "OK1") (pin "1") (pinfunction "A_1") (pintype "passive"))
      (node (ref "R24") (pin "2") (pinfunction "2_2") (pintype "passive"))
    )
    (net (code "90") (name "Net-(OK1-EMIT)") (class "Default")
      (node (ref "OK1") (pin "3") (pinfunction "EMIT_3") (pintype "passive"))
      (node (ref "Q3") (pin "2") (pinfunction "B_2") (pintype "passive"))
    )
    (net (code "91") (name "Net-(OK2-A)") (class "Default")
      (node (ref "OK2") (pin "1") (pinfunction "A_1") (pintype "passive"))
      (node (ref "R25") (pin "2") (pinfunction "2_2") (pintype "passive"))
    )
    (net (code "92") (name "Net-(OK2-EMIT)") (class "Default")
      (node (ref "OK2") (pin "3") (pinfunction "EMIT_3") (pintype "passive"))
      (node (ref "Q4") (pin "2") (pinfunction "B_2") (pintype "passive"))
    )
    (net (code "93") (name "Net-(OK3-A)") (class "Default")
      (node (ref "OK3") (pin "1") (pinfunction "A_1") (pintype "passive"))
      (node (ref "R26") (pin "2") (pinfunction "2_2") (pintype "passive"))
    )
    (net (code "94") (name "Net-(OK3-EMIT)") (class "Default")
      (node (ref "OK3") (pin "3") (pinfunction "EMIT_3") (pintype "passive"))
      (node (ref "Q5") (pin "2") (pinfunction "B_2") (pintype "passive"))
    )
    (net (code "95") (name "Net-(OK4-A)") (class "Default")
      (node (ref "OK4") (pin "1") (pinfunction "A_1") (pintype "passive"))
      (node (ref "R27") (pin "2") (pinfunction "2_2") (pintype "passive"))
    )
    (net (code "96") (name "Net-(OK4-A1)") (class "Default")
      (node (ref "OK4") (pin "4") (pinfunction "A1_4") (pintype "passive"))
      (node (ref "R13") (pin "1") (pinfunction "1_1") (pintype "passive"))
      (node (ref "T1") (pin "G") (pinfunction "G_G") (pintype "passive"))
    )
    (net (code "97") (name "Net-(OK4-A2)") (class "Default")
      (node (ref "OK4") (pin "6") (pinfunction "A2_6") (pintype "passive"))
      (node (ref "R28") (pin "1") (pinfunction "1_1") (pintype "passive"))
    )
    (net (code "98") (name "Net-(OK5-A)") (class "Default")
      (node (ref "OK5") (pin "1") (pinfunction "A_1") (pintype "passive"))
      (node (ref "R29") (pin "2") (pinfunction "2_2") (pintype "passive"))
    )
    (net (code "99") (name "Net-(OK5-A1)") (class "Default")
      (node (ref "OK5") (pin "4") (pinfunction "A1_4") (pintype "passive"))
      (node (ref "T2") (pin "G") (pinfunction "G_G") (pintype "passive"))
    )
    (net (code "100") (name "Net-(OK5-A2)") (class "Default")
      (node (ref "OK5") (pin "6") (pinfunction "A2_6") (pintype "passive"))
      (node (ref "R30") (pin "1") (pinfunction "1_1") (pintype "passive"))
    )
    (net (code "101") (name "Net-(OK6-A)") (class "Default")
      (node (ref "OK6") (pin "1") (pinfunction "A_1") (pintype "passive"))
      (node (ref "R31") (pin "2") (pinfunction "2_2") (pintype "passive"))
    )
    (net (code "102") (name "Net-(OK6-A1)") (class "Default")
      (node (ref "OK6") (pin "4") (pinfunction "A1_4") (pintype "passive"))
      (node (ref "T3") (pin "G") (pinfunction "G_G") (pintype "passive"))
    )
    (net (code "103") (name "Net-(OK6-A2)") (class "Default")
      (node (ref "OK6") (pin "6") (pinfunction "A2_6") (pintype "passive"))
      (node (ref "R32") (pin "1") (pinfunction "1_1") (pintype "passive"))
    )
    (net (code "104") (name "Net-(OK7-A)") (class "Default")
      (node (ref "OK7") (pin "1") (pinfunction "A_1") (pintype "passive"))
      (node (ref "R33") (pin "2") (pinfunction "2_2") (pintype "passive"))
    )
    (net (code "105") (name "Net-(OK7-A1)") (class "Default")
      (node (ref "OK7") (pin "4") (pinfunction "A1_4") (pintype "passive"))
      (node (ref "T4") (pin "G") (pinfunction "G_G") (pintype "passive"))
    )
    (net (code "106") (name "Net-(OK7-A2)") (class "Default")
      (node (ref "OK7") (pin "6") (pinfunction "A2_6") (pintype "passive"))
      (node (ref "R34") (pin "1") (pinfunction "1_1") (pintype "passive"))
    )
    (net (code "107") (name "Net-(OK8-A)") (class "Default")
      (node (ref "OK8") (pin "1") (pinfunction "A_1") (pintype "passive"))
      (node (ref "R35") (pin "2") (pinfunction "2_2") (pintype "passive"))
    )
    (net (code "108") (name "Net-(OK8-EMIT)") (class "Default")
      (node (ref "OK8") (pin "3") (pinfunction "EMIT_3") (pintype "passive"))
      (node (ref "Q6") (pin "2") (pinfunction "B_2") (pintype "passive"))
    )
    (net (code "109") (name "Net-(Q2-B)") (class "Default")
      (node (ref "Q2") (pin "1") (pinfunction "B_1") (pintype "passive"))
      (node (ref "R14") (pin "1") (pinfunction "1_1") (pintype "passive"))
    )
    (net (code "110") (name "Net-(Q2-C)") (class "Default")
      (node (ref "Q2") (pin "3") (pinfunction "C_3") (pintype "passive"))
      (node (ref "R15") (pin "1") (pinfunction "1_1") (pintype "passive"))
    )
    (net (code "111") (name "Net-(R4-Pad2)") (class "Default")
      (node (ref "R4") (pin "2") (pinfunction "2_2") (pintype "passive"))
      (node (ref "U$3") (pin "UART_TX") (pinfunction "UART_TX_UART_TX") (pintype "bidirectional"))
    )
    (net (code "112") (name "Net-(R5-Pad2)") (class "Default")
      (node (ref "R5") (pin "2") (pinfunction "2_2") (pintype "passive"))
      (node (ref "U$3") (pin "UART_RX") (pinfunction "UART_RX_UART_RX") (pintype "bidirectional"))
    )
    (net (code "113") (name "Net-(T1-A1)") (class "Default")
      (node (ref "C14") (pin "1") (pinfunction "1_1") (pintype "passive"))
      (node (ref "R13") (pin "2") (pinfunction "2_2") (pintype "passive"))
      (node (ref "T1") (pin "T1") (pinfunction "A1_T1") (pintype "passive"))
      (node (ref "U$4") (pin "2") (pinfunction "2_2") (pintype "passive"))
    )
    (net (code "114") (name "Net-(T2-A1)") (class "Default")
      (node (ref "C15") (pin "1") (pinfunction "1_1") (pintype "passive"))
      (node (ref "T2") (pin "T1") (pinfunction "A1_T1") (pintype "passive"))
      (node (ref "U$6") (pin "2") (pinfunction "2_2") (pintype "passive"))
    )
    (net (code "115") (name "Net-(T3-A1)") (class "Default")
      (node (ref "C16") (pin "1") (pinfunction "1_1") (pintype "passive"))
      (node (ref "C17") (pin "1") (pinfunction "1_1") (pintype "passive"))
      (node (ref "T3") (pin "T1") (pinfunction "A1_T1") (pintype "passive"))
      (node (ref "U$8") (pin "2") (pinfunction "2_2") (pintype "passive"))
    )
    (net (code "116") (name "Net-(U$1-VBATT)") (class "Default")
      (node (ref "D2") (pin "C") (pinfunction "C_C") (pintype "passive"))
      (node (ref "D3") (pin "C") (pinfunction "C_C") (pintype "passive"))
      (node (ref "R7") (pin "1") (pinfunction "1_1") (pintype "passive"))
      (node (ref "R8") (pin "1") (pinfunction "1_1") (pintype "passive"))
      (node (ref "U$1") (pin "3") (pinfunction "VBATT_3") (pintype "bidirectional"))
      (node (ref "U$1") (pin "8") (pinfunction "VCC_8") (pintype "bidirectional"))
    )
    (net (code "117") (name "Net-(U$1-X1)") (class "Default")
      (node (ref "U$1") (pin "1") (pinfunction "X1_1") (pintype "bidirectional"))
      (node (ref "Y1") (pin "1") (pinfunction "1_1") (pintype "passive"))
    )
    (net (code "118") (name "Net-(U$1-X2)") (class "Default")
      (node (ref "U$1") (pin "2") (pinfunction "X2_2") (pintype "bidirectional"))
      (node (ref "Y1") (pin "2") (pinfunction "2_2") (pintype "passive"))
    )
    (net (code "119") (name "Net-(U$11-ADJ)") (class "Default")
      (node (ref "JP8") (pin "1") (pinfunction "1_1") (pintype "passive"))
      (node (ref "JP8") (pin "2") (pinfunction "2_2") (pintype "passive"))
      (node (ref "U$11") (pin "2") (pinfunction "ADJ_2") (pintype "bidirectional"))
    )
    (net (code "120") (name "Net-(X1A-S)") (class "Default")
      (node (ref "R24") (pin "1") (pinfunction "1_1") (pintype "passive"))
      (node (ref "X1") (pin "1") (pinfunction "S_1") (pintype "passive"))
    )
    (net (code "121") (name "Net-(X1B-S)") (class "Default")
      (node (ref "R25") (pin "1") (pinfunction "1_1") (pintype "passive"))
      (node (ref "X1") (pin "2") (pinfunction "S_2") (pintype "passive"))
    )
    (net (code "122") (name "Net-(X1C-S)") (class "Default")
      (node (ref "R26") (pin "1") (pinfunction "1_1") (pintype "passive"))
      (node (ref "X1") (pin "3") (pinfunction "S_3") (pintype "passive"))
    )
    (net (code "123") (name "Net-(X1D-S)") (class "Default")
      (node (ref "R35") (pin "1") (pinfunction "1_1") (pintype "passive"))
      (node (ref "X1") (pin "4") (pinfunction "S_4") (pintype "passive"))
    )
    (net (code "124") (name "Net-(X2A-S)") (class "Default")
      (node (ref "R27") (pin "1") (pinfunction "1_1") (pintype "passive"))
      (node (ref "X2") (pin "1") (pinfunction "S_1") (pintype "passive"))
    )
    (net (code "125") (name "Net-(X2B-S)") (class "Default")
      (node (ref "R29") (pin "1") (pinfunction "1_1") (pintype "passive"))
      (node (ref "X2") (pin "2") (pinfunction "S_2") (pintype "passive"))
    )
    (net (code "126") (name "Net-(X2C-S)") (class "Default")
      (node (ref "R31") (pin "1") (pinfunction "1_1") (pintype "passive"))
      (node (ref "X2") (pin "3") (pinfunction "S_3") (pintype "passive"))
    )
    (net (code "127") (name "Net-(X2D-S)") (class "Default")
      (node (ref "R33") (pin "1") (pinfunction "1_1") (pintype "passive"))
      (node (ref "X2") (pin "4") (pinfunction "S_4") (pintype "passive"))
    )
    (net (code "128") (name "Net-(X7A-KL)") (class "Default")
      (node (ref "F1") (pin "2") (pinfunction "2_2") (pintype "passive"))
      (node (ref "X7") (pin "1") (pinfunction "KL_1") (pintype "passive"))
    )
    (net (code "129") (name "unconnected-(ATMEGA32U4-D+-Pad4)") (class "Default")
      (node (ref "ATMEGA32U4") (pin "4") (pinfunction "D+_4") (pintype "bidirectional"))
    )
    (net (code "130") (name "unconnected-(ATMEGA32U4-D--Pad3)") (class "Default")
      (node (ref "ATMEGA32U4") (pin "3") (pinfunction "D-_3") (pintype "bidirectional"))
    )
    (net (code "131") (name "unconnected-(K1B-O-PadNC)") (class "Default")
      (node (ref "K1") (pin "NC") (pinfunction "O_NC") (pintype "passive"))
    )
    (net (code "132") (name "unconnected-(K2B-O-PadNC)") (class "Default")
      (node (ref "K2") (pin "NC") (pinfunction "O_NC") (pintype "passive"))
    )
    (net (code "133") (name "unconnected-(K3B-O-PadNC)") (class "Default")
      (node (ref "K3") (pin "NC") (pinfunction "O_NC") (pintype "passive"))
    )
    (net (code "134") (name "unconnected-(K4B-O-PadNC)") (class "Default")
      (node (ref "K4") (pin "NC") (pinfunction "O_NC") (pintype "passive"))
    )
    (net (code "135") (name "unconnected-(U$1-SQW-Pad7)") (class "Default")
      (node (ref "U$1") (pin "7") (pinfunction "SQW_7") (pintype "bidirectional"))
    )
    (net (code "136") (name "unconnected-(U$3-PadNC1)") (class "Default")
      (node (ref "U$3") (pin "NC1") (pinfunction "NC1_NC1") (pintype "bidirectional"))
    )
    (net (code "137") (name "unconnected-(U$3-PadNC2)") (class "Default")
      (node (ref "U$3") (pin "NC2") (pinfunction "NC2_NC2") (pintype "bidirectional"))
    )
    (net (code "138") (name "unconnected-(U$3-PadNC3)") (class "Default")
      (node (ref "U$3") (pin "NC3") (pinfunction "NC3_NC3") (pintype "bidirectional"))
    )
    (net (code "139") (name "unconnected-(U$3-PadNV1)") (class "Default")
      (node (ref "U$3") (pin "NV1") (pinfunction "NV1_NV1") (pintype "bidirectional"))
    )
    (net (code "140") (name "unconnected-(U$3-PadNV2)") (class "Default")
      (node (ref "U$3") (pin "NV2") (pinfunction "NV2_NV2") (pintype "bidirectional"))
    )
    (net (code "141") (name "unconnected-(U$3-PadPIO0)") (class "Default")
      (node (ref "U$3") (pin "PIO0") (pinfunction "PIO0_PIO0") (pintype "bidirectional"))
    )
    (net (code "142") (name "unconnected-(U$3-PadPIO2)") (class "Default")
      (node (ref "U$3") (pin "PIO2") (pinfunction "PIO2_PIO2") (pintype "bidirectional"))
    )
    (net (code "143") (name "unconnected-(U$3-PadPIO3)") (class "Default")
      (node (ref "U$3") (pin "PIO3") (pinfunction "PIO3_PIO3") (pintype "bidirectional"))
    )
    (net (code "144") (name "unconnected-(U$3-PadRESETB)") (class "Default")
      (node (ref "U$3") (pin "RESETB") (pinfunction "RESETB_RESETB") (pintype "bidirectional"))
    )
    (net (code "145") (name "unconnected-(U$3-PadUART_CTS)") (class "Default")
      (node (ref "U$3") (pin "UART_CTS") (pinfunction "UART_CTS_UART_CTS") (pintype "bidirectional"))
    )
    (net (code "146") (name "unconnected-(X6A-S-Pad1)") (class "Default")
      (node (ref "X6") (pin "1") (pinfunction "S_1") (pintype "passive"))
    )
  )
)
